# rev_n_v24.net
KiCad netlist of a schematic drawn in EAGLE
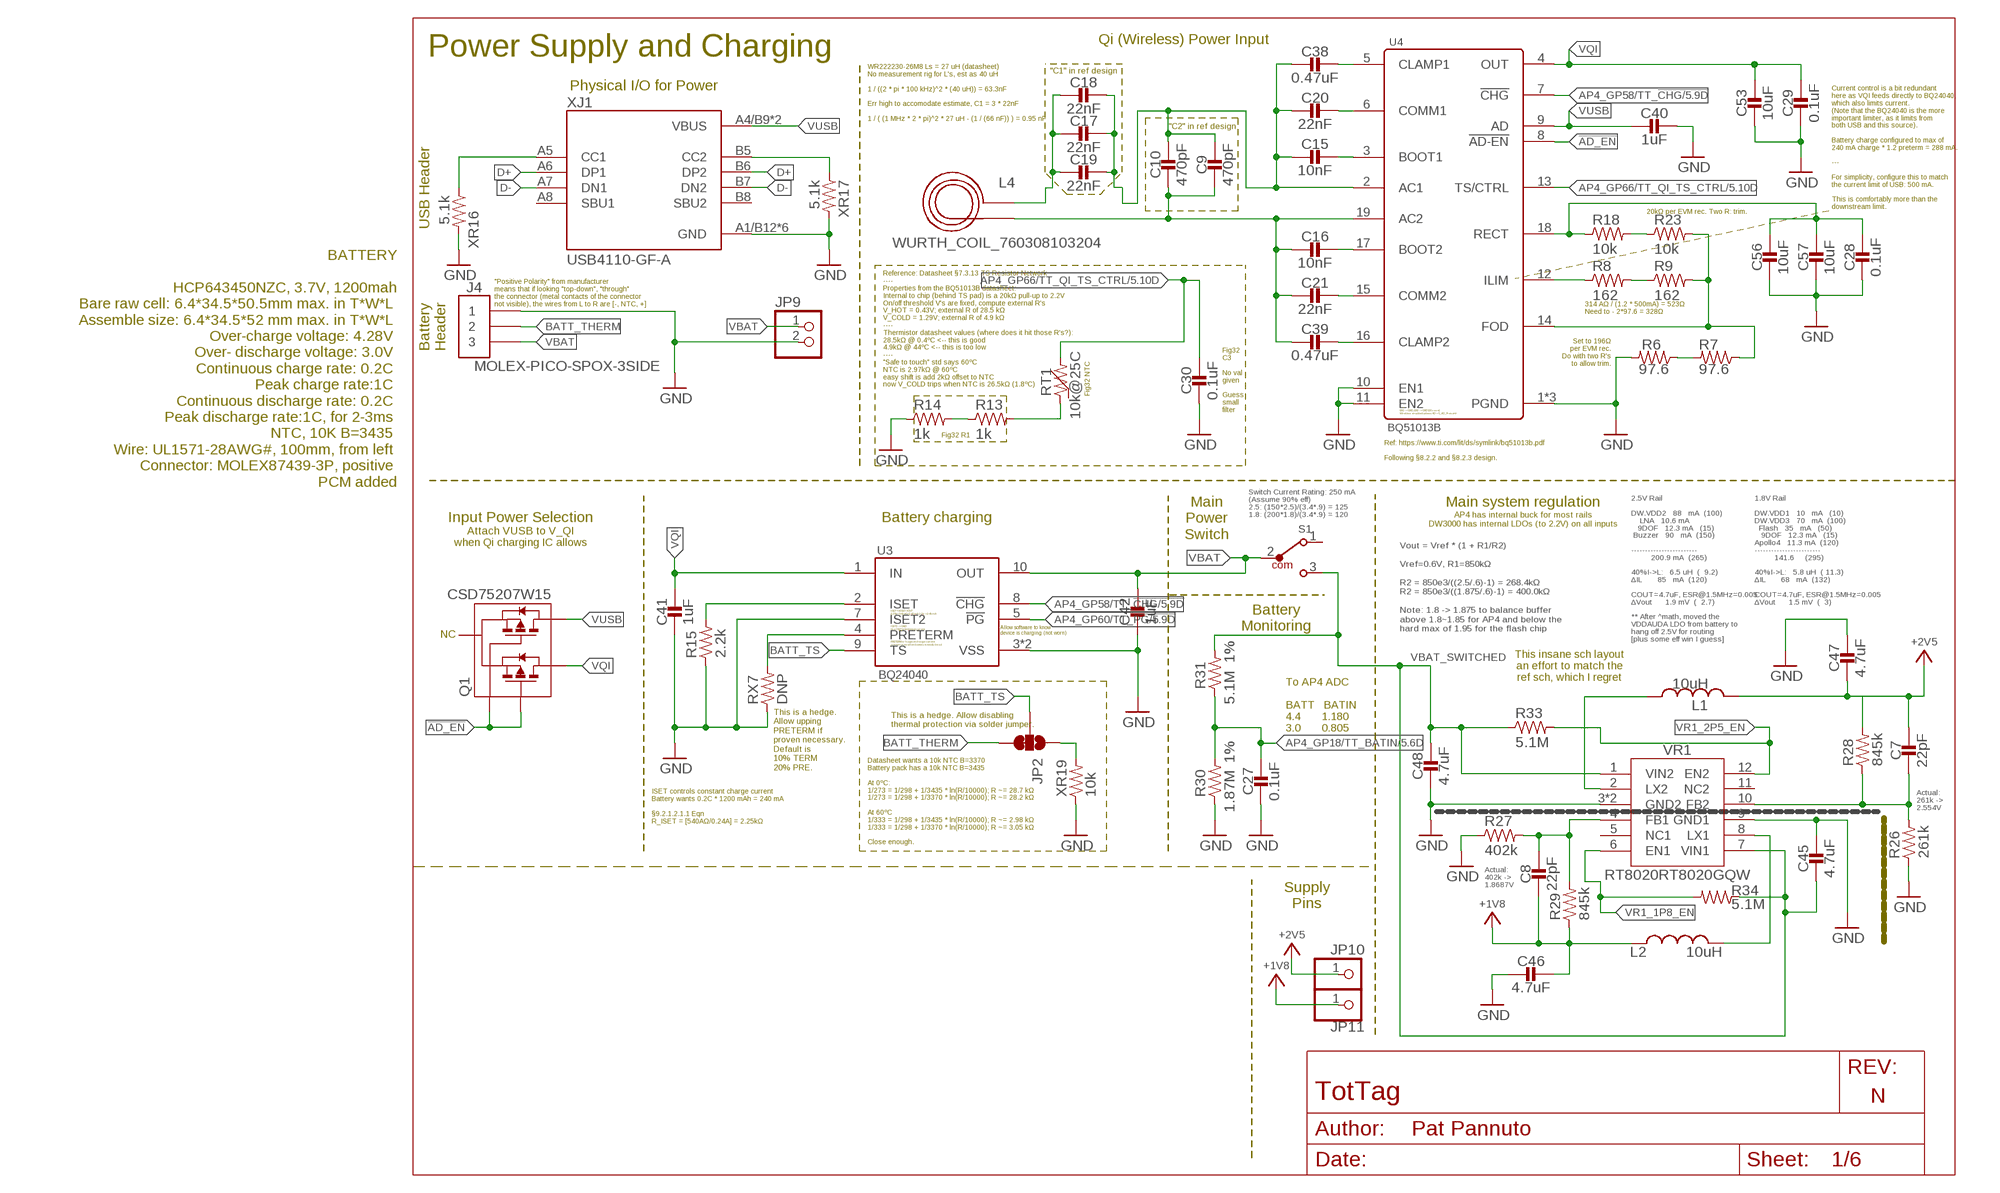
[diagram p0: schematic, sheet 1]
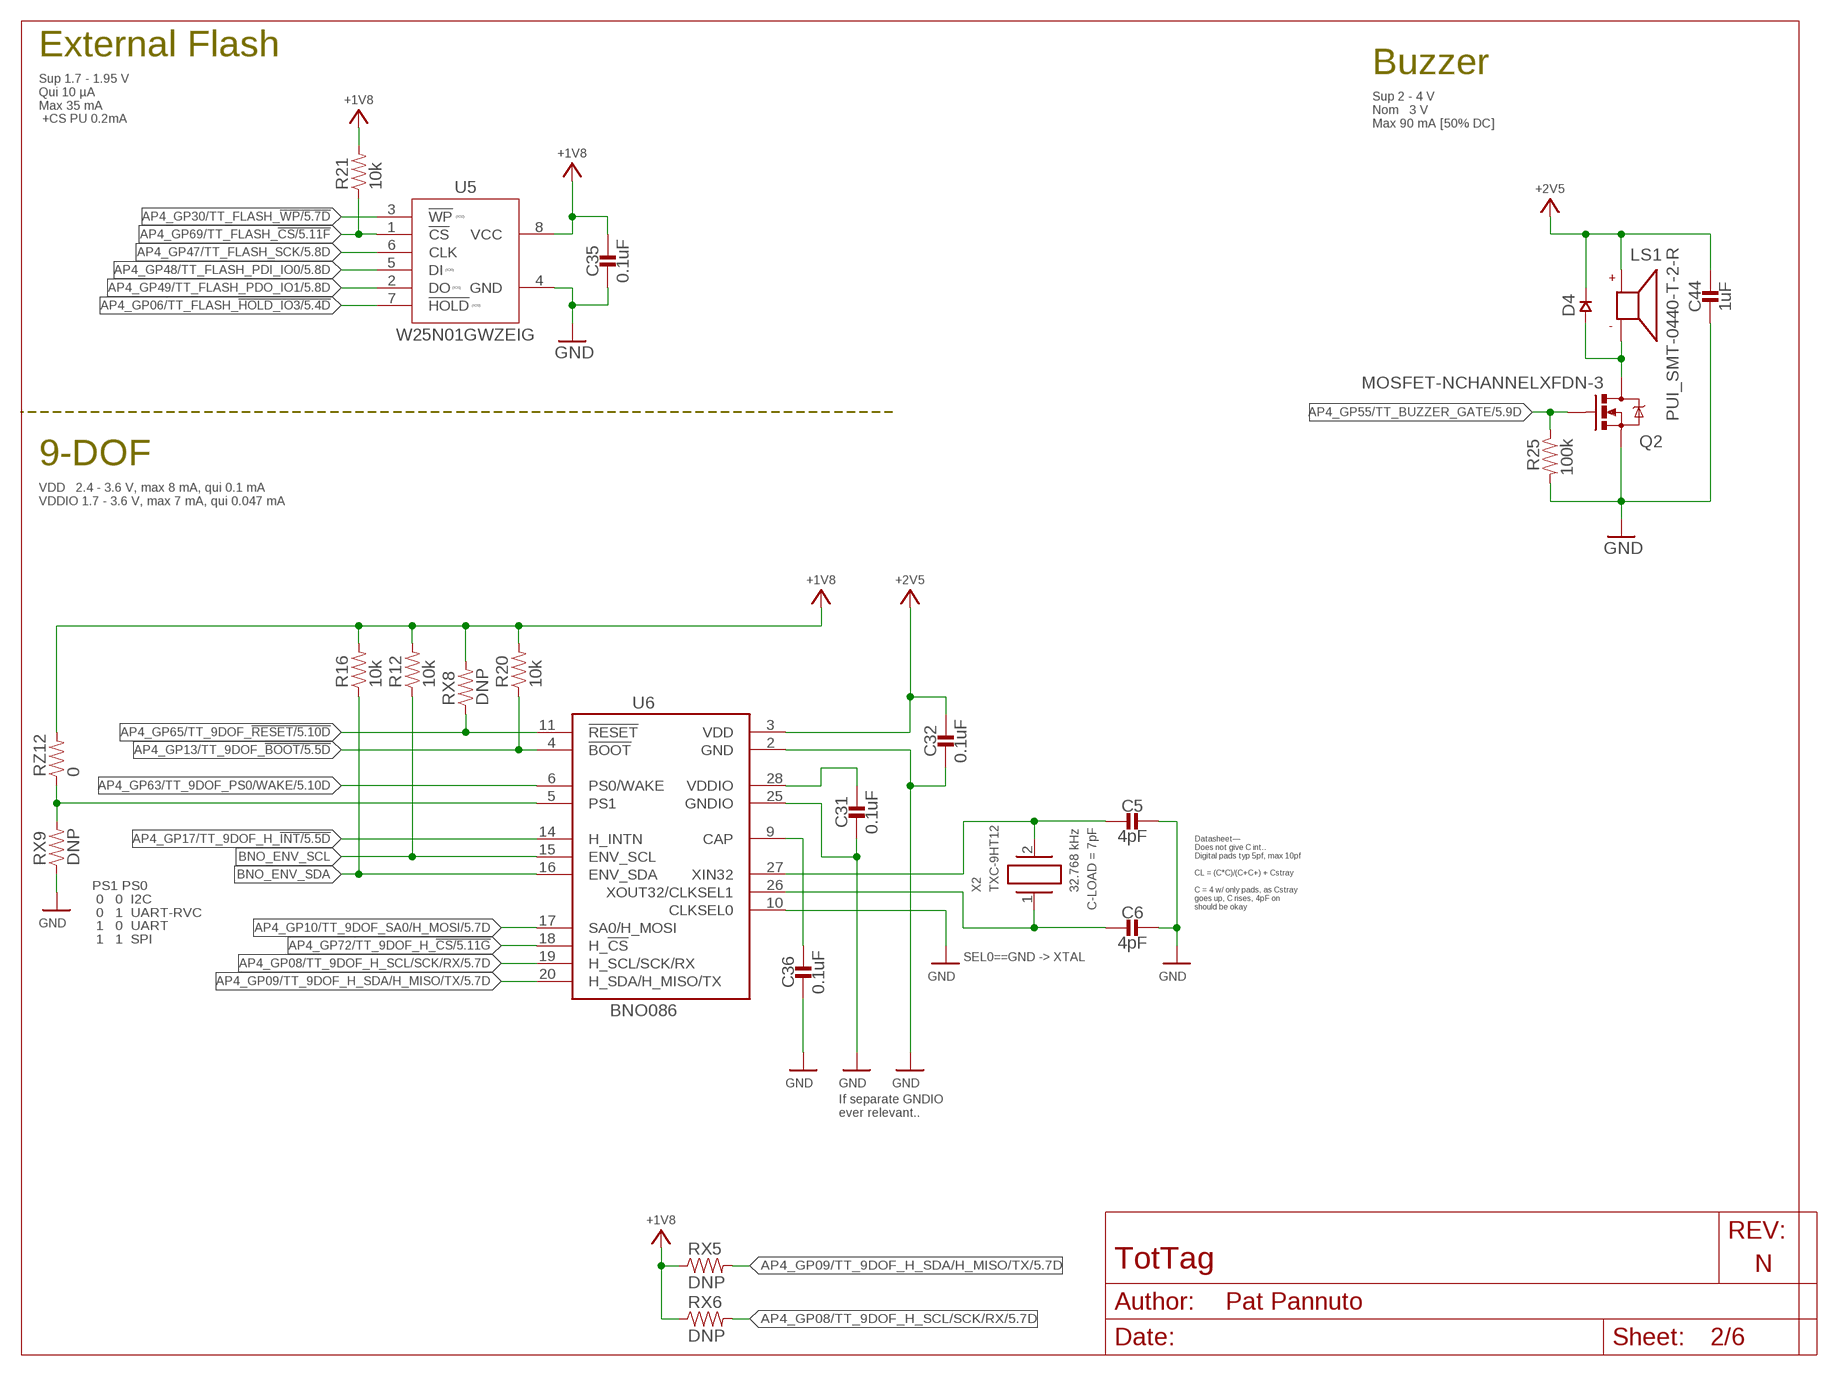
[diagram p1: schematic, sheet 2]
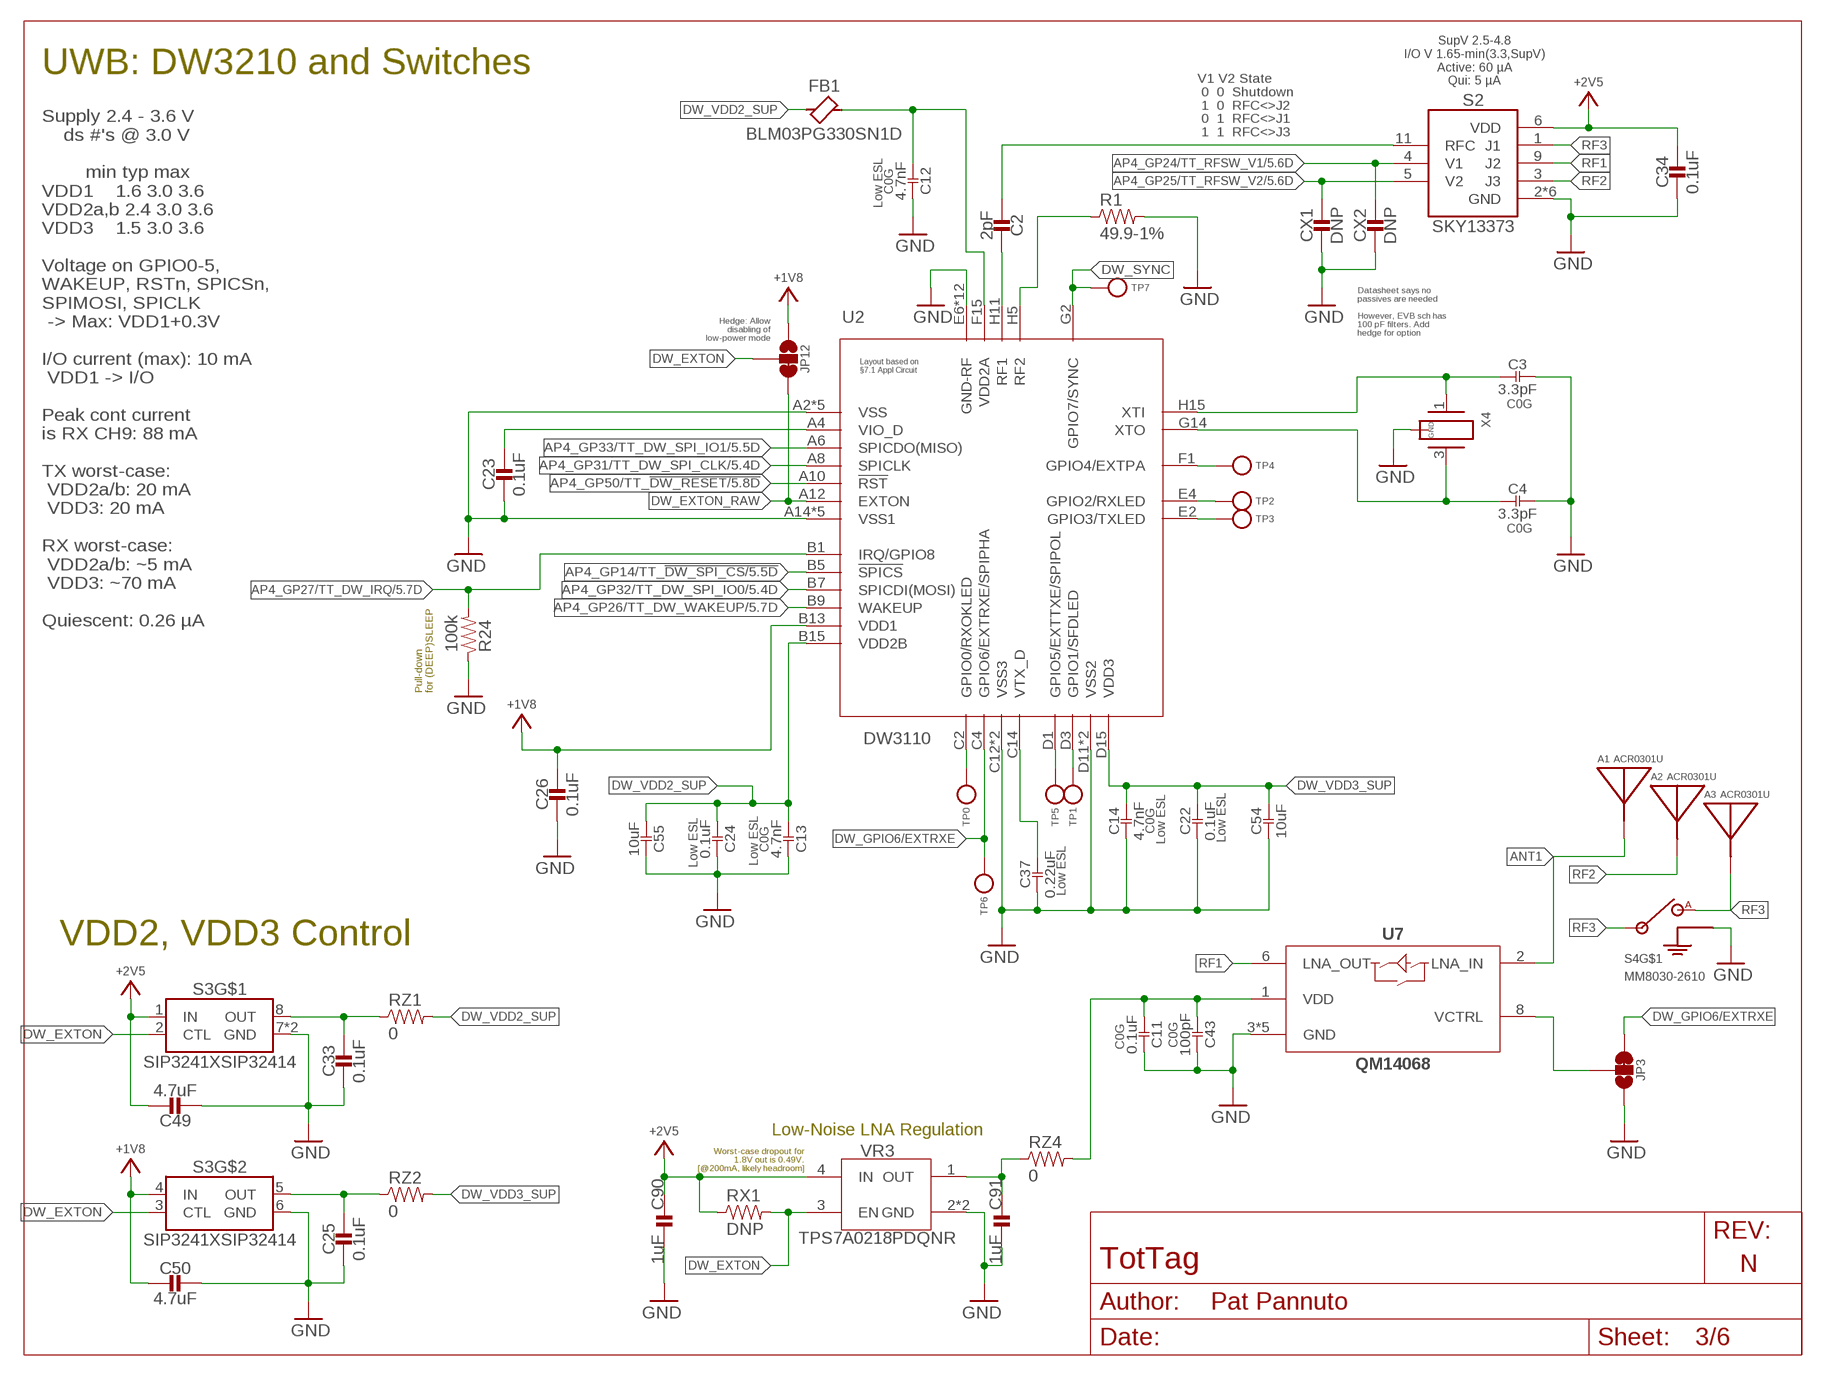
[diagram p2: schematic, sheet 3]
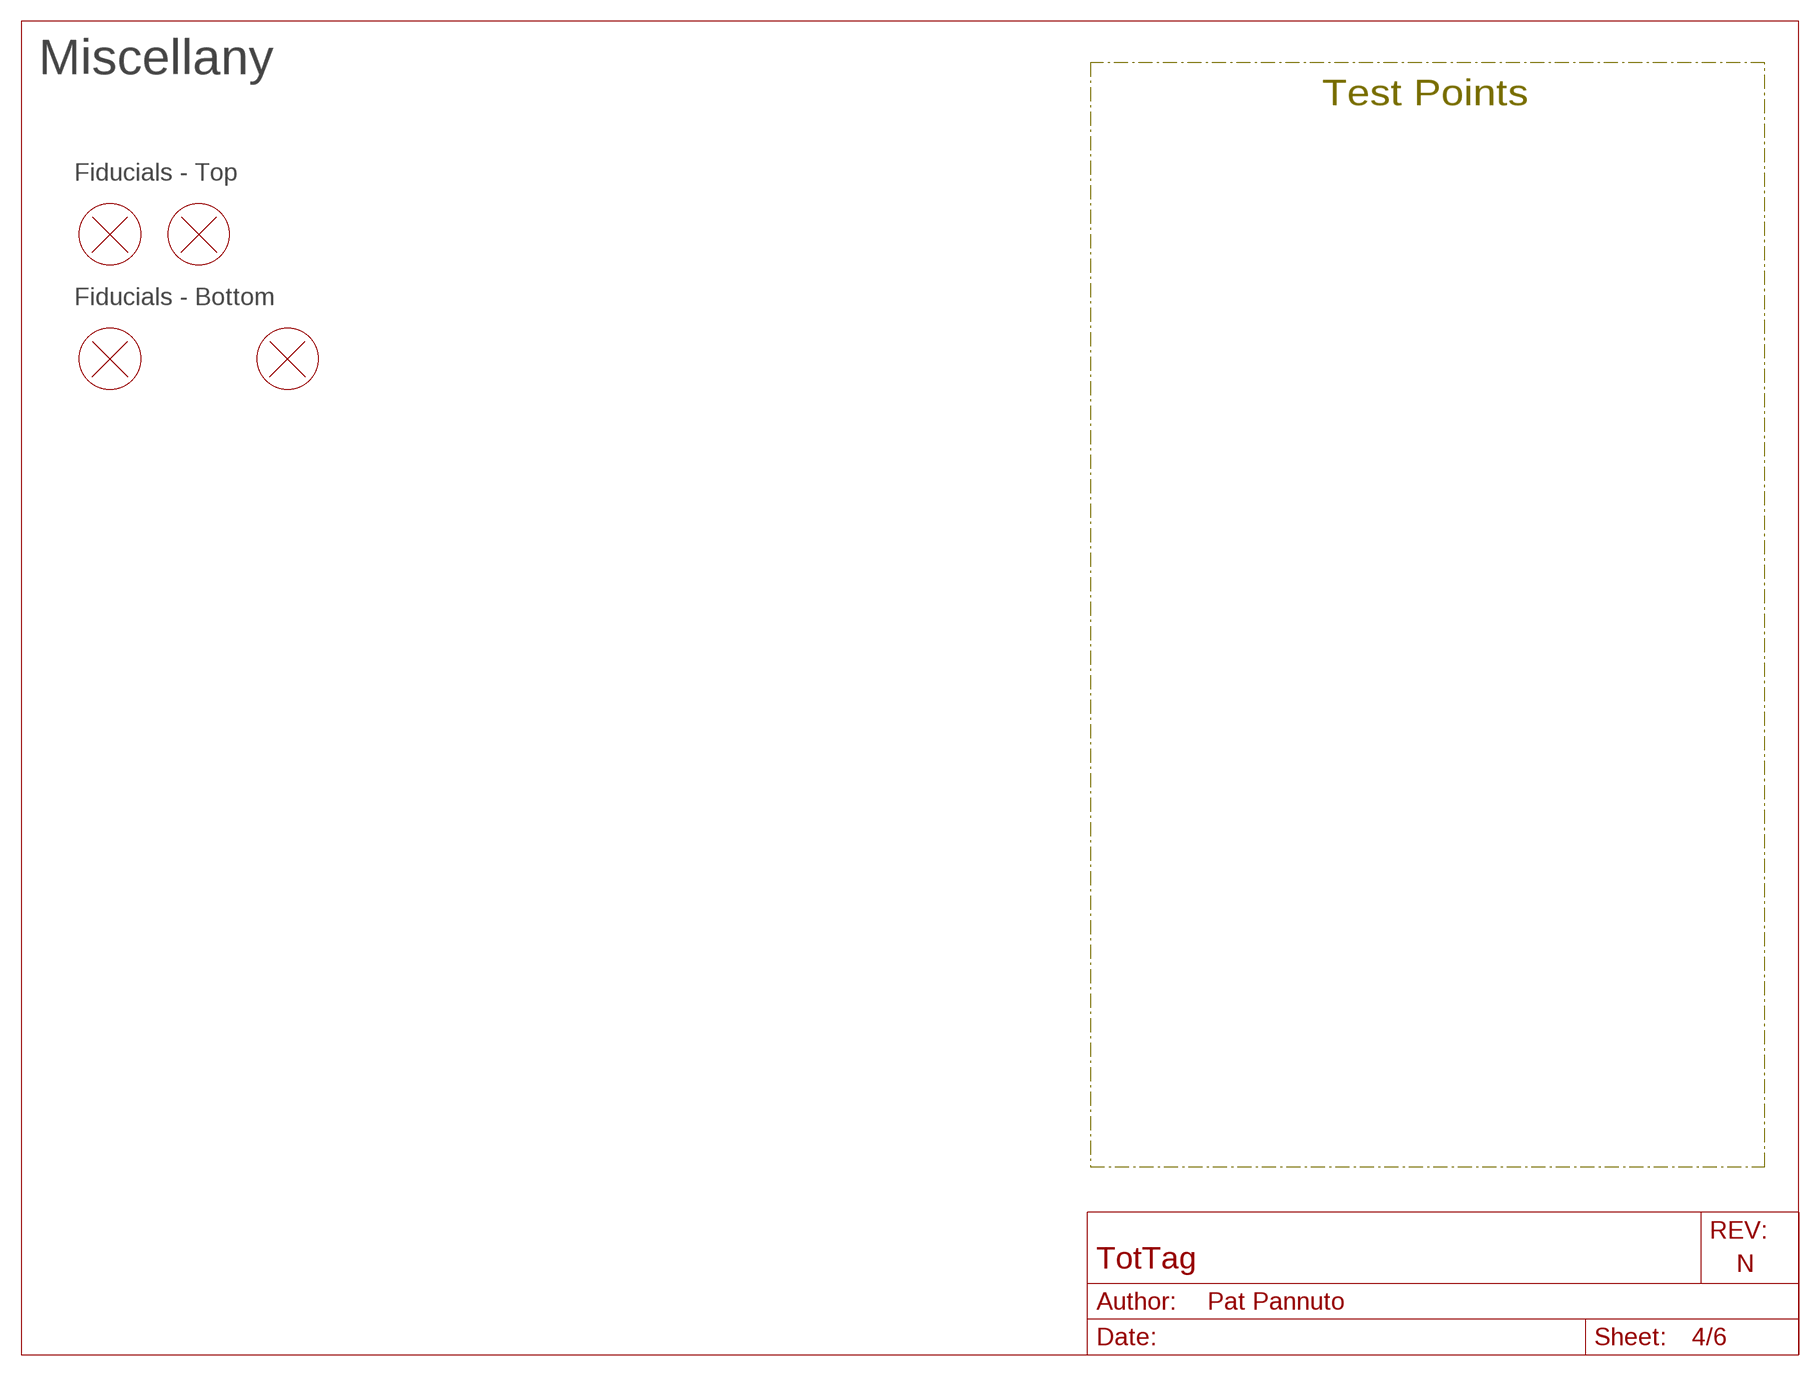
[diagram p3: schematic, sheet 4]
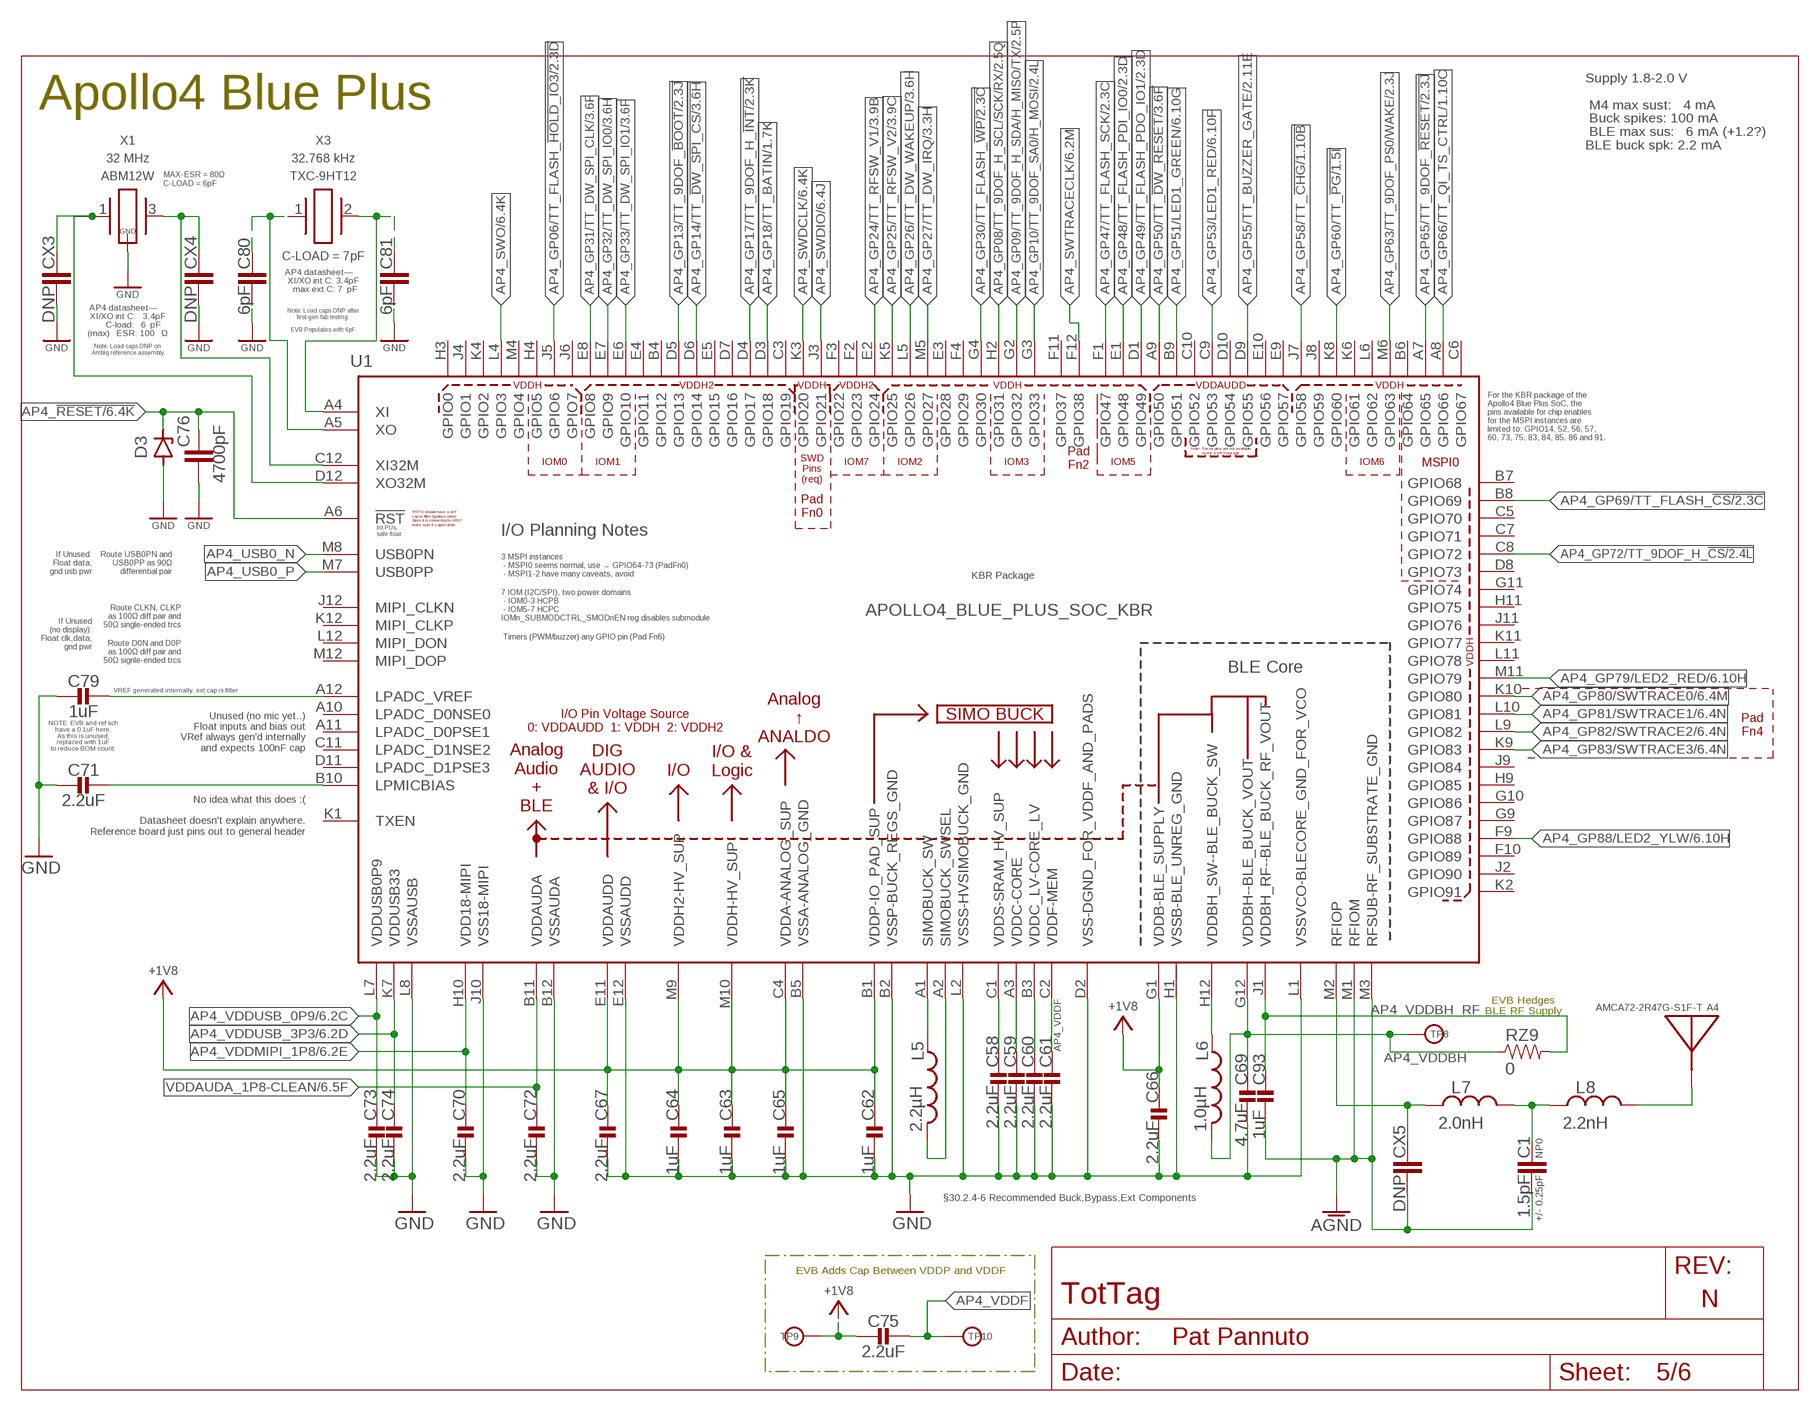
[diagram p4: schematic, sheet 5]
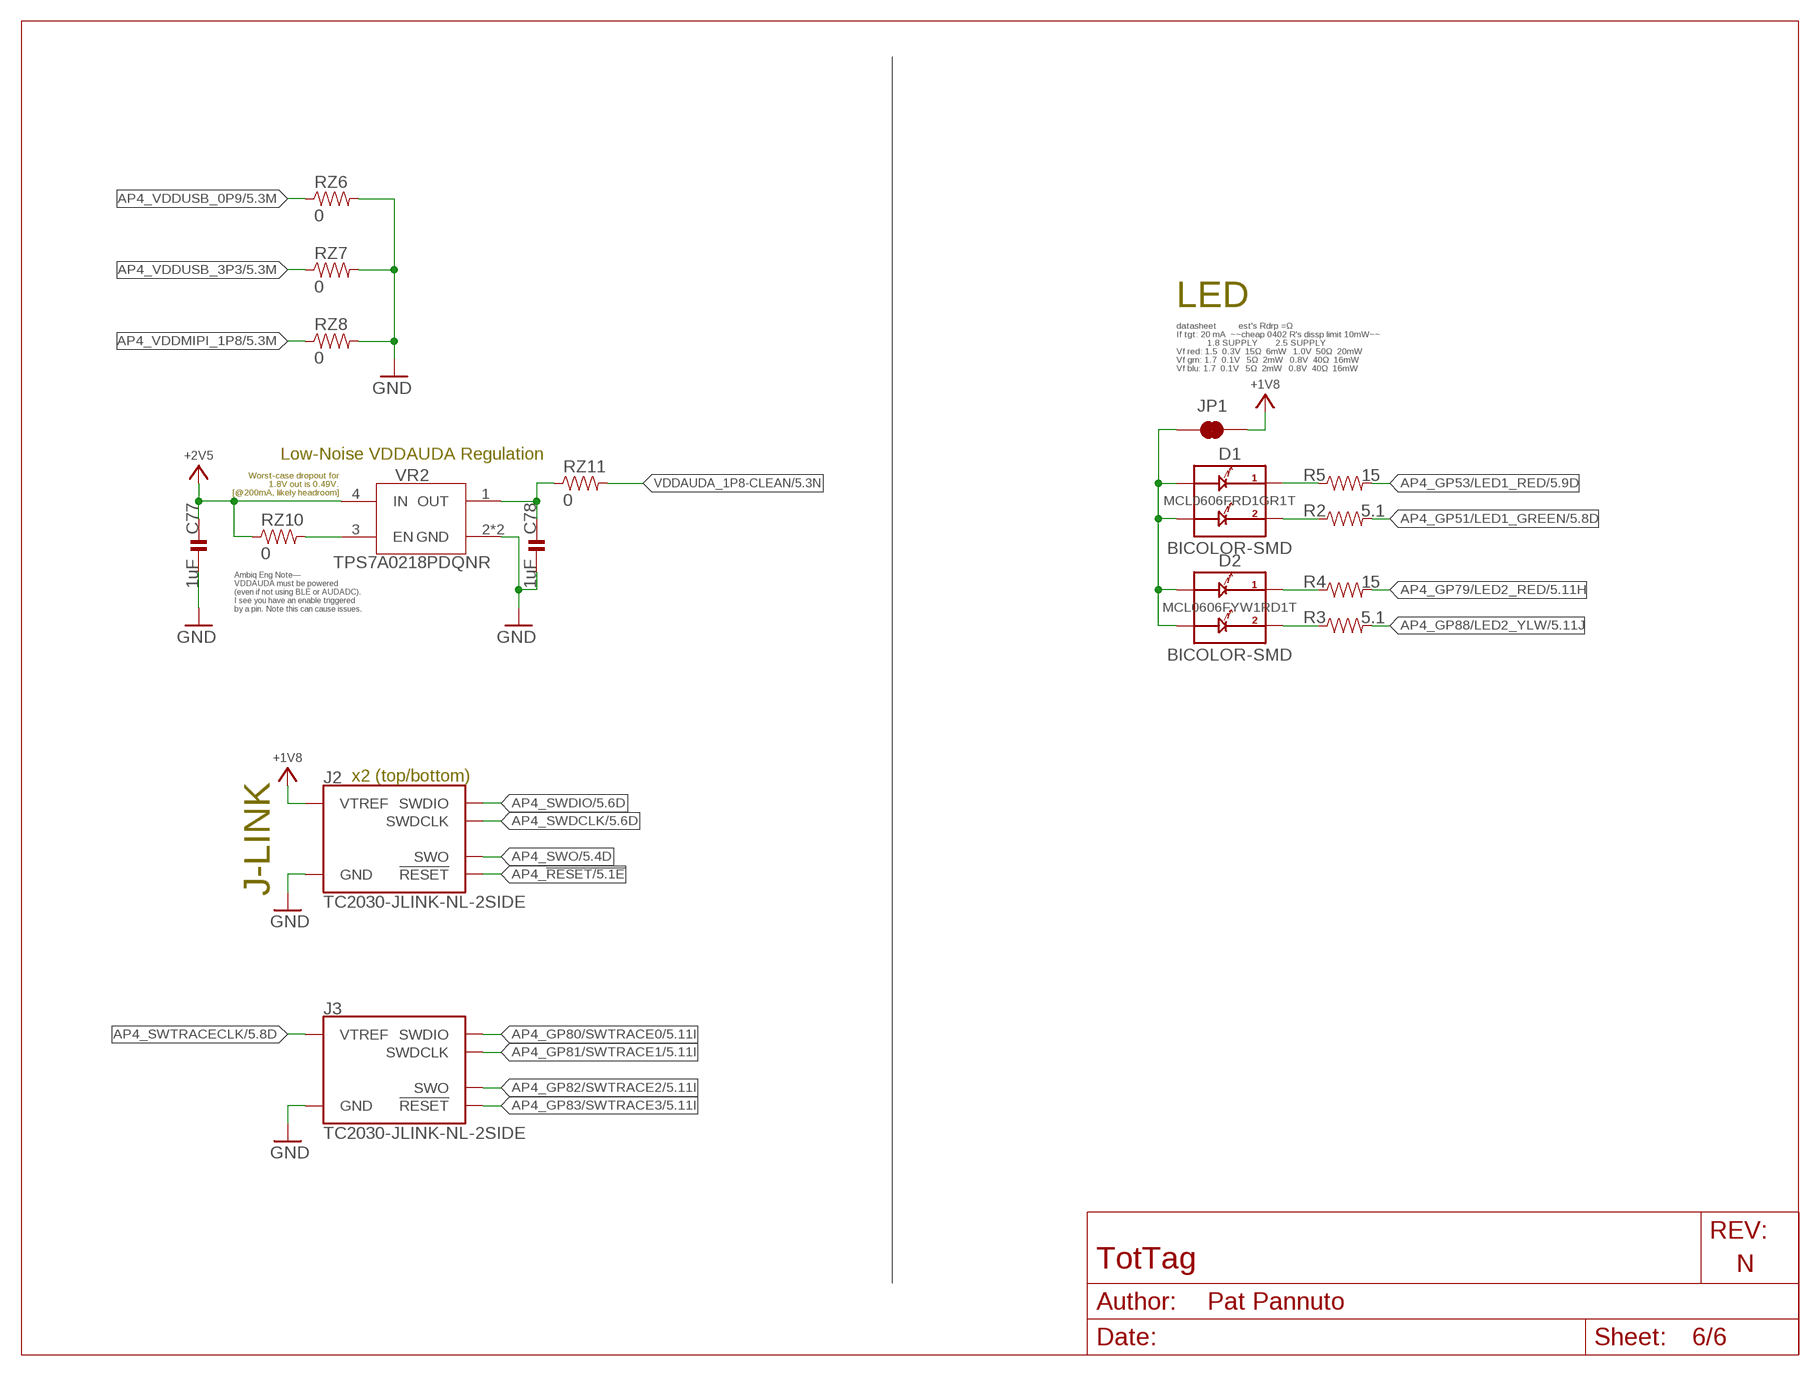
[diagram p5: schematic, sheet 6]

(export (version "E")
  (design (tool "Eeschema 10.0.6"))
  (components
    (comp (ref "FD1")
      (value "FIDUCIAL")
      (footprint "eagle-import:FIDUCIAL_1MM-CU_2MM-MASK")
      (libsource (lib "eagle-import") (part "FIDUCIAL"))
    )
    (comp (ref "FD2")
      (value "FIDUCIAL")
      (footprint "eagle-import:FIDUCIAL_1MM-CU_2MM-MASK")
      (libsource (lib "eagle-import") (part "FIDUCIAL"))
    )
    (comp (ref "FD4")
      (value "FIDUCIAL")
      (footprint "eagle-import:FIDUCIAL_1MM-CU_2MM-MASK")
      (libsource (lib "eagle-import") (part "FIDUCIAL"))
    )
    (comp (ref "FD6")
      (value "FIDUCIAL")
      (footprint "eagle-import:FIDUCIAL_1MM-CU_2MM-MASK")
      (libsource (lib "eagle-import") (part "FIDUCIAL"))
    )
    (comp (ref "C7")
      (value "22pF")
      (footprint "eagle-import:0201_CAP")
      (fields (field (name "MPN") "GRM0335C1H220FA01D"))
      (libsource (lib "eagle-import") (part "passives_20904581_CAPACITOR0201_CAP"))
    )
    (comp (ref "C8")
      (value "22pF")
      (footprint "eagle-import:0201_CAP")
      (fields (field (name "MPN") "GRM0335C1H220FA01D"))
      (libsource (lib "eagle-import") (part "passives_20904581_CAPACITOR0201_CAP"))
    )
    (comp (ref "C9")
      (value "470pF")
      (footprint "eagle-import:0402_CAP")
      (description "CAP CER 470PF 50V C0G/NP0 0402")
      (fields (field (name "MANUFACTURER") "Murata") (field (name "MPN") "GRM1555C1H471JA01J"))
      (libsource (lib "eagle-import") (part "passives_20904581_CAPACITOR0402_CAP"))
    )
    (comp (ref "C10")
      (value "470pF")
      (footprint "eagle-import:0402_CAP")
      (description "CAP CER 470PF 50V C0G/NP0 0402")
      (fields (field (name "MANUFACTURER") "Murata") (field (name "MPN") "GRM1555C1H471JA01J"))
      (libsource (lib "eagle-import") (part "passives_20904581_CAPACITOR0402_CAP"))
    )
    (comp (ref "C15")
      (value "10nF")
      (footprint "eagle-import:0402_CAP")
      (fields (field (name "MPN") "GRM155R71H103KA88J"))
      (libsource (lib "eagle-import") (part "passives_20904581_CAPACITOR0402_CAP"))
    )
    (comp (ref "C16")
      (value "10nF")
      (footprint "eagle-import:0402_CAP")
      (fields (field (name "MPN") "GRM155R71H103KA88J"))
      (libsource (lib "eagle-import") (part "passives_20904581_CAPACITOR0402_CAP"))
    )
    (comp (ref "C17")
      (value "22nF")
      (footprint "eagle-import:0402_CAP")
      (fields (field (name "MPN") "GRM155R71E223JA61D"))
      (libsource (lib "eagle-import") (part "passives_20904581_CAPACITOR0402_CAP"))
    )
    (comp (ref "C18")
      (value "22nF")
      (footprint "eagle-import:0402_CAP")
      (fields (field (name "MPN") "GRM155R71E223JA61D"))
      (libsource (lib "eagle-import") (part "passives_20904581_CAPACITOR0402_CAP"))
    )
    (comp (ref "C19")
      (value "22nF")
      (footprint "eagle-import:0402_CAP")
      (fields (field (name "MPN") "GRM155R71E223JA61D"))
      (libsource (lib "eagle-import") (part "passives_20904581_CAPACITOR0402_CAP"))
    )
    (comp (ref "C20")
      (value "22nF")
      (footprint "eagle-import:0402_CAP")
      (fields (field (name "MPN") "CC0402ZRY5V8BB223"))
      (libsource (lib "eagle-import") (part "passives_20904581_CAPACITOR0402_CAP"))
    )
    (comp (ref "C21")
      (value "22nF")
      (footprint "eagle-import:0402_CAP")
      (fields (field (name "MPN") "CC0402ZRY5V8BB223"))
      (libsource (lib "eagle-import") (part "passives_20904581_CAPACITOR0402_CAP"))
    )
    (comp (ref "C27")
      (value "0.1uF")
      (footprint "eagle-import:0402_CAP")
      (fields (field (name "MPN") "GRM155R71C104KA88J "))
      (libsource (lib "eagle-import") (part "CAPACITOR0402_CAP"))
    )
    (comp (ref "C28")
      (value "0.1uF")
      (footprint "eagle-import:0402_CAP")
      (fields (field (name "MPN") "GRM155R71C104KA88J "))
      (libsource (lib "eagle-import") (part "CAPACITOR0402_CAP"))
    )
    (comp (ref "C29")
      (value "0.1uF")
      (footprint "eagle-import:0402_CAP")
      (fields (field (name "MPN") "GRM155R71C104KA88J "))
      (libsource (lib "eagle-import") (part "CAPACITOR0402_CAP"))
    )
    (comp (ref "C30")
      (value "0.1uF")
      (footprint "eagle-import:0402_CAP")
      (fields (field (name "MPN") "GRM155R71C104KA88J "))
      (libsource (lib "eagle-import") (part "CAPACITOR0402_CAP"))
    )
    (comp (ref "C38")
      (value "0.47uF")
      (footprint "eagle-import:0402_CAP")
      (fields (field (name "MPN") "GRT155R61E474ME01D"))
      (libsource (lib "eagle-import") (part "passives_20904581_CAPACITOR0402_CAP"))
    )
    (comp (ref "C39")
      (value "0.47uF")
      (footprint "eagle-import:0402_CAP")
      (fields (field (name "MPN") "GRT155R61E474ME01D"))
      (libsource (lib "eagle-import") (part "passives_20904581_CAPACITOR0402_CAP"))
    )
    (comp (ref "C40")
      (value "1uF")
      (footprint "eagle-import:0402_CAP")
      (fields (field (name "MPN") "GRM155R70J105KA12J"))
      (libsource (lib "eagle-import") (part "CAPACITOR0402_CAP"))
    )
    (comp (ref "C41")
      (value "1uF")
      (footprint "eagle-import:0402_CAP")
      (fields (field (name "MPN") "GRM155R70J105KA12J"))
      (libsource (lib "eagle-import") (part "CAPACITOR0402_CAP"))
    )
    (comp (ref "C42")
      (value "1uF")
      (footprint "eagle-import:0402_CAP")
      (fields (field (name "MPN") "GRM155R70J105KA12J"))
      (libsource (lib "eagle-import") (part "CAPACITOR0402_CAP"))
    )
    (comp (ref "C45")
      (value "4.7uF")
      (footprint "eagle-import:0603_CAP")
      (fields (field (name "MPN") "C1608X7S1A475K080AC"))
      (libsource (lib "eagle-import") (part "passives_20904581_CAPACITOR0603_CAP"))
    )
    (comp (ref "C46")
      (value "4.7uF")
      (footprint "eagle-import:0603_CAP")
      (fields (field (name "MPN") "C1608X7S1A475K080AC"))
      (libsource (lib "eagle-import") (part "passives_20904581_CAPACITOR0603_CAP"))
    )
    (comp (ref "C47")
      (value "4.7uF")
      (footprint "eagle-import:0603_CAP")
      (fields (field (name "MPN") "C1608X7S1A475K080AC"))
      (libsource (lib "eagle-import") (part "passives_20904581_CAPACITOR0603_CAP"))
    )
    (comp (ref "C48")
      (value "4.7uF")
      (footprint "eagle-import:0603_CAP")
      (fields (field (name "MPN") "C1608X7S1A475K080AC"))
      (libsource (lib "eagle-import") (part "passives_20904581_CAPACITOR0603_CAP"))
    )
    (comp (ref "C53")
      (value "10uF")
      (footprint "eagle-import:0603_CAP")
      (fields (field (name "MPN") "CM105X5R106M25AT"))
      (libsource (lib "eagle-import") (part "passives_20904581_CAPACITOR0603_CAP"))
    )
    (comp (ref "C56")
      (value "10uF")
      (footprint "eagle-import:0603_CAP")
      (fields (field (name "MPN") "CM105X5R106M25AT"))
      (libsource (lib "eagle-import") (part "passives_20904581_CAPACITOR0603_CAP"))
    )
    (comp (ref "C57")
      (value "10uF")
      (footprint "eagle-import:0603_CAP")
      (fields (field (name "MPN") "CM105X5R106M25AT"))
      (libsource (lib "eagle-import") (part "passives_20904581_CAPACITOR0603_CAP"))
    )
    (comp (ref "J4")
      (value "MOLEX-PICO-SPOX-3SIDE")
      (footprint "eagle-import:MOLEX-PICO-SPOX-3_SIDE")
      (libsource (lib "eagle-import") (part "MOLEX-PICO-SPOX-3SIDE"))
    )
    (comp (ref "JP2")
      (value "JUMPER-SMT_3_1-NC_TRACE_SILK")
      (footprint "eagle-import:SMT-JUMPER_3_1-NC_TRACE_SILK")
      (libsource (lib "eagle-import") (part "JUMPER-SMT_3_1-NC_TRACE_SILK"))
    )
    (comp (ref "JP9")
      (value "PINHD-1X2")
      (footprint "eagle-import:1X02")
      (libsource (lib "eagle-import") (part "PINHD-1X2"))
    )
    (comp (ref "JP10")
      (value "PINHD-1X1")
      (footprint "eagle-import:1X01")
      (libsource (lib "eagle-import") (part "PINHD-1X1"))
    )
    (comp (ref "JP11")
      (value "PINHD-1X1")
      (footprint "eagle-import:1X01")
      (libsource (lib "eagle-import") (part "PINHD-1X1"))
    )
    (comp (ref "L1")
      (value "10uH")
      (footprint "eagle-import:NRX3015")
      (fields (field (name "MANUFACTURER") "TAIYO YUDEN") (field (name "MPN") "NR3015T100M"))
      (libsource (lib "eagle-import") (part "INDUCTORNRX3015"))
    )
    (comp (ref "L2")
      (value "10uH")
      (footprint "eagle-import:NRX3015")
      (fields (field (name "MANUFACTURER") "TAIYO YUDEN") (field (name "MPN") "NR3015T100M"))
      (libsource (lib "eagle-import") (part "INDUCTORNRX3015"))
    )
    (comp (ref "L4")
      (value "WURTH_COIL_760308103204")
      (footprint "eagle-import:WURTH_COIL_760308103204")
      (fields (field (name "MANUFACTURER") "Würth Elektronik") (field (name "MPN") "760308103204"))
      (libsource (lib "eagle-import") (part "WURTH_COIL_760308103204"))
    )
    (comp (ref "Q1")
      (value "CSD75207W15")
      (footprint "eagle-import:DSBGA")
      (fields (field (name "MANUFACTURER") "TEXAS INSTRUMENTS"))
      (libsource (lib "eagle-import") (part "CSD75207W15"))
    )
    (comp (ref "R6")
      (value "97.6")
      (footprint "eagle-import:0402_RES")
      (fields (field (name "MPN") "RMCF0402FT97R6"))
      (libsource (lib "eagle-import") (part "passives_20904581_RESISTOR0402_RES"))
    )
    (comp (ref "R7")
      (value "97.6")
      (footprint "eagle-import:0402_RES")
      (fields (field (name "MPN") "RMCF0402FT97R6"))
      (libsource (lib "eagle-import") (part "passives_20904581_RESISTOR0402_RES"))
    )
    (comp (ref "R8")
      (value "162")
      (footprint "eagle-import:0402_RES")
      (fields (field (name "MPN") "RMCF0402FT162R"))
      (libsource (lib "eagle-import") (part "passives_20904581_RESISTOR0402_RES"))
    )
    (comp (ref "R9")
      (value "162")
      (footprint "eagle-import:0402_RES")
      (fields (field (name "MPN") "RMCF0402FT162R"))
      (libsource (lib "eagle-import") (part "passives_20904581_RESISTOR0402_RES"))
    )
    (comp (ref "R13")
      (value "1k")
      (footprint "eagle-import:0402_RES")
      (libsource (lib "eagle-import") (part "RESISTOR0402_RES"))
    )
    (comp (ref "R14")
      (value "1k")
      (footprint "eagle-import:0402_RES")
      (libsource (lib "eagle-import") (part "RESISTOR0402_RES"))
    )
    (comp (ref "R15")
      (value "2.2k")
      (footprint "eagle-import:0402_RES")
      (fields (field (name "MPN") "RMCF0402JT2K20"))
      (libsource (lib "eagle-import") (part "passives_20904581_RESISTOR0402_RES"))
    )
    (comp (ref "R18")
      (value "10k")
      (footprint "eagle-import:0402_RES")
      (fields (field (name "MPN") "RC0402JR-0710KL"))
      (libsource (lib "eagle-import") (part "RESISTOR0402_RES"))
    )
    (comp (ref "R23")
      (value "10k")
      (footprint "eagle-import:0402_RES")
      (fields (field (name "MPN") "RC0402JR-0710KL"))
      (libsource (lib "eagle-import") (part "RESISTOR0402_RES"))
    )
    (comp (ref "R26")
      (value "261k")
      (footprint "eagle-import:0201_RES")
      (fields (field (name "MPN") "ERJ-1GNF2613C"))
      (libsource (lib "eagle-import") (part "passives_20904581_RESISTOR0201_RES"))
    )
    (comp (ref "R27")
      (value "402k")
      (footprint "eagle-import:0201_RES")
      (fields (field (name "MPN") "ERJ-1GNF4023C"))
      (libsource (lib "eagle-import") (part "passives_20904581_RESISTOR0201_RES"))
    )
    (comp (ref "R28")
      (value "845k")
      (footprint "eagle-import:0201_RES")
      (fields (field (name "MPN") "ERJ-1GNF8453C"))
      (libsource (lib "eagle-import") (part "passives_20904581_RESISTOR0201_RES"))
    )
    (comp (ref "R29")
      (value "845k")
      (footprint "eagle-import:0201_RES")
      (fields (field (name "MPN") "ERJ-1GNF8453C"))
      (libsource (lib "eagle-import") (part "passives_20904581_RESISTOR0201_RES"))
    )
    (comp (ref "R30")
      (value "1.87M")
      (footprint "eagle-import:0402_RES")
      (fields (field (name "MPN") "RMCF0402FT1M87") (field (name "TOLERANCE") "1%"))
      (libsource (lib "eagle-import") (part "RESISTOR0402_RES"))
    )
    (comp (ref "R31")
      (value "5.1M")
      (footprint "eagle-import:0402_RES")
      (fields (field (name "MPN") "RMCF0402FT5M10") (field (name "TOLERANCE") "1%"))
      (libsource (lib "eagle-import") (part "RESISTOR0402_RES"))
    )
    (comp (ref "R33")
      (value "5.1M")
      (footprint "eagle-import:0402_RES")
      (fields (field (name "MPN") "RMCF0402FT5M10"))
      (libsource (lib "eagle-import") (part "RESISTOR0402_RES"))
    )
    (comp (ref "R34")
      (value "5.1M")
      (footprint "eagle-import:0402_RES")
      (fields (field (name "MPN") "RMCF0402FT5M10"))
      (libsource (lib "eagle-import") (part "RESISTOR0402_RES"))
    )
    (comp (ref "RT1")
      (value "10k@25C")
      (footprint "eagle-import:0402_RES")
      (fields (field (name "MPN") "NCU15XH103F60RC"))
      (libsource (lib "eagle-import") (part "THERMISTOR0402"))
    )
    (comp (ref "RX7")
      (value "DNP")
      (footprint "eagle-import:0402_RES")
      (libsource (lib "eagle-import") (part "passives_20904581_RESISTOR0402_RES"))
    )
    (comp (ref "S1")
      (value "450404015514")
      (footprint "eagle-import:450404015514")
      (libsource (lib "eagle-import") (part "450404015514"))
    )
    (comp (ref "U3")
      (value "BQ24040")
      (footprint "eagle-import:DSQ0010A")
      (fields (field (name "MPN") "BQ24040DSQR"))
      (libsource (lib "eagle-import") (part "BQ24040"))
    )
    (comp (ref "U4")
      (value "BQ51013B")
      (footprint "eagle-import:RHL0020A")
      (fields (field (name "MPN") "BQ51013BRHLR"))
      (libsource (lib "eagle-import") (part "BQ51013B"))
    )
    (comp (ref "VR1")
      (value "RT8020RT8020GQW")
      (footprint "eagle-import:SON45P300X300X80-13T160X250N")
      (fields (field (name "MANUFACTURER") "RichTek") (field (name "MPN") "RT8020GQW"))
      (libsource (lib "eagle-import") (part "RT8020RT8020GQW"))
    )
    (comp (ref "XJ1")
      (value "USB4110-GF-A")
      (footprint "eagle-import:GCT_USB4110-GF-A")
      (fields (field (name "MF") "GCT"))
      (libsource (lib "eagle-import") (part "USB4110-GF-A"))
    )
    (comp (ref "XR16")
      (value "5.1k")
      (footprint "eagle-import:0402_RES")
      (fields (field (name "MPN") "RMCF0402FT5K10"))
      (libsource (lib "eagle-import") (part "passives_20904581_RESISTOR0402_RES"))
    )
    (comp (ref "XR17")
      (value "5.1k")
      (footprint "eagle-import:0402_RES")
      (fields (field (name "MPN") "RMCF0402FT5K10"))
      (libsource (lib "eagle-import") (part "passives_20904581_RESISTOR0402_RES"))
    )
    (comp (ref "XR19")
      (value "10k")
      (footprint "eagle-import:0402_RES")
      (fields (field (name "MPN") "RC0402JR-0710KL"))
      (libsource (lib "eagle-import") (part "RESISTOR0402_RES"))
    )
    (comp (ref "C5")
      (value "4pF")
      (footprint "eagle-import:0201_CAP")
      (fields (field (name "MANUFACTURER") "Murata") (field (name "MPN") "GRM0335C1H4R0BA01D"))
      (libsource (lib "eagle-import") (part "passives_20904581_CAPACITOR0201_CAP"))
    )
    (comp (ref "C6")
      (value "4pF")
      (footprint "eagle-import:0201_CAP")
      (fields (field (name "MANUFACTURER") "Murata") (field (name "MPN") "GRM0335C1H4R0BA01D"))
      (libsource (lib "eagle-import") (part "passives_20904581_CAPACITOR0201_CAP"))
    )
    (comp (ref "C31")
      (value "0.1uF")
      (footprint "eagle-import:0402_CAP")
      (fields (field (name "MPN") "CL05A104KP5NNNC"))
      (libsource (lib "eagle-import") (part "passives_20904581_CAPACITOR0402_CAP"))
    )
    (comp (ref "C32")
      (value "0.1uF")
      (footprint "eagle-import:0402_CAP")
      (fields (field (name "MPN") "CL05A104KP5NNNC"))
      (libsource (lib "eagle-import") (part "passives_20904581_CAPACITOR0402_CAP"))
    )
    (comp (ref "C35")
      (value "0.1uF")
      (footprint "eagle-import:0402_CAP")
      (fields (field (name "MPN") "CL05A104KP5NNNC"))
      (libsource (lib "eagle-import") (part "passives_20904581_CAPACITOR0402_CAP"))
    )
    (comp (ref "C36")
      (value "0.1uF")
      (footprint "eagle-import:0402_CAP")
      (fields (field (name "MPN") "CL05A104KP5NNNC"))
      (libsource (lib "eagle-import") (part "CAPACITOR0402_CAP"))
    )
    (comp (ref "C44")
      (value "1uF")
      (footprint "eagle-import:0402_CAP")
      (fields (field (name "MPN") "GRM155R70J105KA12J"))
      (libsource (lib "eagle-import") (part "CAPACITOR0402_CAP"))
    )
    (comp (ref "D4")
      (value "DIODE0402")
      (footprint "eagle-import:0402_DIODE")
      (fields (field (name "MPN") "CDSQR400B-HF"))
      (libsource (lib "eagle-import") (part "DIODE0402"))
    )
    (comp (ref "LS1")
      (value "PUI_SMT-0440-T-2-R")
      (footprint "eagle-import:SMT-0440-T-2-R")
      (fields (field (name "MPN") "SMT-0440-T-2-R"))
      (libsource (lib "eagle-import") (part "PUI_SMT-0440-T-2-R"))
    )
    (comp (ref "Q2")
      (value "MOSFET-NCHANNELXFDN-3")
      (footprint "eagle-import:XFDFN-3")
      (libsource (lib "eagle-import") (part "MOSFET-NCHANNELXFDN-3"))
    )
    (comp (ref "R12")
      (value "10k")
      (footprint "eagle-import:0402_RES")
      (fields (field (name "MPN") "RC0402JR-0710KL"))
      (libsource (lib "eagle-import") (part "RESISTOR0402_RES"))
    )
    (comp (ref "R16")
      (value "10k")
      (footprint "eagle-import:0402_RES")
      (fields (field (name "MPN") "RC0402JR-0710KL"))
      (libsource (lib "eagle-import") (part "RESISTOR0402_RES"))
    )
    (comp (ref "R20")
      (value "10k")
      (footprint "eagle-import:0402_RES")
      (fields (field (name "MPN") "RC0402JR-0710KL"))
      (libsource (lib "eagle-import") (part "RESISTOR0402_RES"))
    )
    (comp (ref "R21")
      (value "10k")
      (footprint "eagle-import:0402_RES")
      (fields (field (name "MPN") "RC0402JR-0710KL"))
      (libsource (lib "eagle-import") (part "RESISTOR0402_RES"))
    )
    (comp (ref "R25")
      (value "100k")
      (footprint "eagle-import:0402_RES")
      (fields (field (name "MPN") "RT0402BRE07100KL"))
      (libsource (lib "eagle-import") (part "RESISTOR0402_RES"))
    )
    (comp (ref "RX5")
      (value "DNP")
      (footprint "eagle-import:0603-RES")
      (libsource (lib "eagle-import") (part "passives_20904581_RESISTOR0603_RES"))
    )
    (comp (ref "RX6")
      (value "DNP")
      (footprint "eagle-import:0603-RES")
      (libsource (lib "eagle-import") (part "passives_20904581_RESISTOR0603_RES"))
    )
    (comp (ref "RX8")
      (value "DNP")
      (footprint "eagle-import:0603-RES")
      (libsource (lib "eagle-import") (part "passives_20904581_RESISTOR0603_RES"))
    )
    (comp (ref "RX9")
      (value "DNP")
      (footprint "eagle-import:0603-RES")
      (libsource (lib "eagle-import") (part "passives_20904581_RESISTOR0603_RES"))
    )
    (comp (ref "RZ12")
      (value "0")
      (footprint "eagle-import:0402_RES")
      (fields (field (name "MPN") "RMCF0402ZT0R00"))
      (libsource (lib "eagle-import") (part "passives_20904581_RESISTOR0402_RES"))
    )
    (comp (ref "U5")
      (value "W25N01GWZEIG")
      (footprint "eagle-import:WSON127P800X600X80-9T430X340N")
      (fields (field (name "MANUFACTURER") "Winbond"))
      (libsource (lib "eagle-import") (part "W25N01GWZEIG"))
    )
    (comp (ref "U6")
      (value "BNO086")
      (footprint "eagle-import:LGA28R0P510X4_5P2X3P8X1")
      (fields (field (name "MANUFACTURER") "CEVA Technologies, Inc."))
      (libsource (lib "eagle-import") (part "BNO086"))
    )
    (comp (ref "X2")
      (value "TXC-9HT12")
      (footprint "eagle-import:TXC-9HT12")
      (fields
        (field (name "C-LOAD") "7pF")
        (field (name "FREQUENCY") "32.768 kHz")
        (field (name "MANUFACTURER") "TXC Corp")
        (field (name "MPN") "9HT12-32.768KDZY-T")
      )
      (libsource (lib "eagle-import") (part "TXC-9HT12"))
    )
    (comp (ref "A1")
      (value "ACR0301U")
      (footprint "eagle-import:ACR0301U")
      (fields (field (name "MANUFACTURER") "Abracon"))
      (libsource (lib "eagle-import") (part "ACR0301U"))
    )
    (comp (ref "A2")
      (value "ACR0301U")
      (footprint "eagle-import:ACR0301U")
      (fields (field (name "MANUFACTURER") "Abracon"))
      (libsource (lib "eagle-import") (part "ACR0301U"))
    )
    (comp (ref "A3")
      (value "ACR0301U")
      (footprint "eagle-import:ACR0301U")
      (fields (field (name "MANUFACTURER") "Abracon"))
      (libsource (lib "eagle-import") (part "ACR0301U"))
    )
    (comp (ref "C2")
      (value "2pF")
      (footprint "eagle-import:0201_CAP")
      (fields (field (name "MPN") "CBR02C209A5GAC"))
      (libsource (lib "eagle-import") (part "CAPACITOR0201_CAP"))
    )
    (comp (ref "C3")
      (value "3.3pF")
      (footprint "eagle-import:SMD_2012M-0805US-C")
      (fields
        (field (name "EIA") "C0G")
        (field (name "MANUFACTURER") "KYOCERA AVX")
        (field (name "MPN") "600F3R3BT250XT")
      )
      (libsource (lib "eagle-import") (part "C0805US"))
    )
    (comp (ref "C4")
      (value "3.3pF")
      (footprint "eagle-import:SMD_2012M-0805US-C")
      (fields
        (field (name "EIA") "C0G")
        (field (name "MANUFACTURER") "KYOCERA AVX")
        (field (name "MPN") "600F3R3BT250XT")
      )
      (libsource (lib "eagle-import") (part "C0805US"))
    )
    (comp (ref "C11")
      (value "0.1uF")
      (footprint "eagle-import:SMD_3216M-1206US-C")
      (fields (field (name "EIA") "C0G") (field (name "MPN") "GRM31C5C1H104JA01L"))
      (libsource (lib "eagle-import") (part "C1206US"))
    )
    (comp (ref "C12")
      (value "4.7nF")
      (footprint "eagle-import:SMD_1608M-0603US-C")
      (fields
        (field (name "EIA") "C0G")
        (field (name "FEATURES") "Low ESL")
        (field (name "MANUFACTURER") "KEMET")
        (field (name "MPN") "C0603C472J5GAC7867")
      )
      (libsource (lib "eagle-import") (part "C0603US"))
    )
    (comp (ref "C13")
      (value "4.7nF")
      (footprint "eagle-import:SMD_1608M-0603US-C")
      (fields
        (field (name "EIA") "C0G")
        (field (name "FEATURES") "Low ESL")
        (field (name "MANUFACTURER") "KEMET")
        (field (name "MPN") "C0603C472J5GAC7867")
      )
      (libsource (lib "eagle-import") (part "C0603US"))
    )
    (comp (ref "C14")
      (value "4.7nF")
      (footprint "eagle-import:SMD_1608M-0603US-C")
      (fields
        (field (name "EIA") "C0G")
        (field (name "FEATURES") "Low ESL")
        (field (name "MANUFACTURER") "KEMET")
        (field (name "MPN") "C0603C472J5GAC7867")
      )
      (libsource (lib "eagle-import") (part "C0603US"))
    )
    (comp (ref "C22")
      (value "0.1uF")
      (footprint "eagle-import:SMD_1608M-0603US-C")
      (fields (field (name "FEATURES") "Low ESL") (field (name "MPN") "C1608X7R1H104K080AA"))
      (libsource (lib "eagle-import") (part "C0603US"))
    )
    (comp (ref "C23")
      (value "0.1uF")
      (footprint "eagle-import:0402_CAP")
      (fields (field (name "MPN") "CL05A104KP5NNNC"))
      (libsource (lib "eagle-import") (part "passives_20904581_CAPACITOR0402_CAP"))
    )
    (comp (ref "C24")
      (value "0.1uF")
      (footprint "eagle-import:SMD_1608M-0603US-C")
      (fields (field (name "FEATURES") "Low ESL") (field (name "MPN") "C1608X7R1H104K080AA"))
      (libsource (lib "eagle-import") (part "C0603US"))
    )
    (comp (ref "C25")
      (value "0.1uF")
      (footprint "eagle-import:0402_CAP")
      (fields (field (name "MPN") "CL05A104KP5NNNC"))
      (libsource (lib "eagle-import") (part "passives_20904581_CAPACITOR0402_CAP"))
    )
    (comp (ref "C26")
      (value "0.1uF")
      (footprint "eagle-import:0402_CAP")
      (fields (field (name "MPN") "CL05A104KP5NNNC"))
      (libsource (lib "eagle-import") (part "passives_20904581_CAPACITOR0402_CAP"))
    )
    (comp (ref "C33")
      (value "0.1uF")
      (footprint "eagle-import:0402_CAP")
      (fields (field (name "MPN") "CL05A104KP5NNNC"))
      (libsource (lib "eagle-import") (part "passives_20904581_CAPACITOR0402_CAP"))
    )
    (comp (ref "C34")
      (value "0.1uF")
      (footprint "eagle-import:0402_CAP")
      (fields (field (name "MPN") "CL05A104KP5NNNC"))
      (libsource (lib "eagle-import") (part "passives_20904581_CAPACITOR0402_CAP"))
    )
    (comp (ref "C37")
      (value "0.22uF")
      (footprint "eagle-import:SMD_1608M-0603US-C")
      (fields (field (name "FEATURES") "Low ESL") (field (name "MPN") "C1608X7R1H224K080AB"))
      (libsource (lib "eagle-import") (part "C0603US"))
    )
    (comp (ref "C43")
      (value "100pF")
      (footprint "eagle-import:SMD_1005M-0402US-C")
      (fields (field (name "EIA") "C0G") (field (name "MPN") "C0402C101J3GACTU"))
      (libsource (lib "eagle-import") (part "C0402US"))
    )
    (comp (ref "C49")
      (value "4.7uF")
      (footprint "eagle-import:0603_CAP")
      (fields (field (name "MPN") "C1608X7S1A475K080AC"))
      (libsource (lib "eagle-import") (part "passives_20904581_CAPACITOR0603_CAP"))
    )
    (comp (ref "C50")
      (value "4.7uF")
      (footprint "eagle-import:0603_CAP")
      (fields (field (name "MPN") "C1608X7S1A475K080AC"))
      (libsource (lib "eagle-import") (part "passives_20904581_CAPACITOR0603_CAP"))
    )
    (comp (ref "C54")
      (value "10uF")
      (footprint "eagle-import:SMD_1608M-0603US-C")
      (fields (field (name "MPN") "CM105X5R106M25AT"))
      (libsource (lib "eagle-import") (part "C0603US"))
    )
    (comp (ref "C55")
      (value "10uF")
      (footprint "eagle-import:SMD_1608M-0603US-C")
      (fields (field (name "MPN") "CM105X5R106M25AT"))
      (libsource (lib "eagle-import") (part "C0603US"))
    )
    (comp (ref "C90")
      (value "1uF")
      (footprint "eagle-import:0201_CAP")
      (fields (field (name "MANUFACTURER") "Murata") (field (name "MPN") "GRM033R61A105ME44D"))
      (libsource (lib "eagle-import") (part "passives_20904581_CAPACITOR0201_CAP"))
    )
    (comp (ref "C91")
      (value "1uF")
      (footprint "eagle-import:0201_CAP")
      (fields (field (name "MANUFACTURER") "Murata") (field (name "MPN") "GRM033R61A105ME44D"))
      (libsource (lib "eagle-import") (part "passives_20904581_CAPACITOR0201_CAP"))
    )
    (comp (ref "CX1")
      (value "DNP")
      (footprint "eagle-import:0603_CAP")
      (libsource (lib "eagle-import") (part "passives_20904581_CAPACITOR0603_CAP"))
    )
    (comp (ref "CX2")
      (value "DNP")
      (footprint "eagle-import:0603_CAP")
      (libsource (lib "eagle-import") (part "passives_20904581_CAPACITOR0603_CAP"))
    )
    (comp (ref "FB1")
      (value "BLM03PG330SN1D")
      (footprint "eagle-import:0201_FB")
      (fields (field (name "MANUFACTURER") "Murata"))
      (libsource (lib "eagle-import") (part "FERRITE_BEAD0201"))
    )
    (comp (ref "JP3")
      (value "JUMPER-SMT_3_1-NC_TRACE_SILK")
      (footprint "eagle-import:SMT-JUMPER_3_1-NC_TRACE_SILK")
      (libsource (lib "eagle-import") (part "JUMPER-SMT_3_1-NC_TRACE_SILK"))
    )
    (comp (ref "JP12")
      (value "JUMPER-SMT_3_1-NC_TRACE_SILK")
      (footprint "eagle-import:SMT-JUMPER_3_1-NC_TRACE_SILK")
      (libsource (lib "eagle-import") (part "JUMPER-SMT_3_1-NC_TRACE_SILK"))
    )
    (comp (ref "R1")
      (value "49.9-1%")
      (footprint "eagle-import:0201_RES")
      (fields (field (name "MPN") "ERJ-1GNF49R9C"))
      (libsource (lib "eagle-import") (part "passives_20904581_RESISTOR0201_RES"))
    )
    (comp (ref "R24")
      (value "100k")
      (footprint "eagle-import:0402_RES")
      (fields (field (name "MPN") "RT0402BRE07100KL"))
      (libsource (lib "eagle-import") (part "RESISTOR0402_RES"))
    )
    (comp (ref "RX1")
      (value "DNP")
      (footprint "eagle-import:0603-RES")
      (libsource (lib "eagle-import") (part "passives_20904581_RESISTOR0603_RES"))
    )
    (comp (ref "RZ1")
      (value "0")
      (footprint "eagle-import:0603-RES")
      (fields (field (name "MPN") "RMCF0603ZT0R00"))
      (libsource (lib "eagle-import") (part "passives_20904581_RESISTOR0603_RES"))
    )
    (comp (ref "RZ2")
      (value "0")
      (footprint "eagle-import:0603-RES")
      (fields (field (name "MPN") "RMCF0603ZT0R00"))
      (libsource (lib "eagle-import") (part "passives_20904581_RESISTOR0603_RES"))
    )
    (comp (ref "RZ4")
      (value "0")
      (footprint "eagle-import:0402_RES")
      (fields (field (name "MPN") "RMCF0402ZT0R00"))
      (libsource (lib "eagle-import") (part "passives_20904581_RESISTOR0402_RES"))
    )
    (comp (ref "S2")
      (value "SKY13373")
      (footprint "eagle-import:SKY13373")
      (fields (field (name "MANUFACTURER") "Skyworks") (field (name "MPN") "SKY13373-460LF"))
      (libsource (lib "eagle-import") (part "SKY13373"))
    )
    (comp (ref "S3")
      (value "SIP3241XSIP32414")
      (footprint "eagle-import:TDFN2X2X0P6-8")
      (fields (field (name "MANUFACTURER") "Vishay") (field (name "MPN") "SIP32414DNP-T1-GE4"))
      (libsource (lib "eagle-import") (part "SIP3241XSIP32414"))
    )
    (comp (ref "S4")
      (value "MM8030-2610")
      (footprint "eagle-import:MM8030-2610")
      (fields (field (name "MANUFACTURER") "Murata"))
      (libsource (lib "eagle-import") (part "MM8030-2610"))
    )
    (comp (ref "TP0")
      (value "TEST-POINT")
      (footprint "eagle-import:PAD.03X.03")
      (libsource (lib "eagle-import") (part "TEST-POINT"))
    )
    (comp (ref "TP1")
      (value "TEST-POINT")
      (footprint "eagle-import:PAD.03X.03")
      (libsource (lib "eagle-import") (part "TEST-POINT"))
    )
    (comp (ref "TP2")
      (value "TEST-POINT")
      (footprint "eagle-import:PAD.03X.03")
      (libsource (lib "eagle-import") (part "TEST-POINT"))
    )
    (comp (ref "TP3")
      (value "TEST-POINT")
      (footprint "eagle-import:PAD.03X.03")
      (libsource (lib "eagle-import") (part "TEST-POINT"))
    )
    (comp (ref "TP4")
      (value "TEST-POINT")
      (footprint "eagle-import:PAD.03X.03")
      (libsource (lib "eagle-import") (part "TEST-POINT"))
    )
    (comp (ref "TP5")
      (value "TEST-POINT")
      (footprint "eagle-import:PAD.03X.03")
      (libsource (lib "eagle-import") (part "TEST-POINT"))
    )
    (comp (ref "TP6")
      (value "TEST-POINT")
      (footprint "eagle-import:PAD.03X.03")
      (libsource (lib "eagle-import") (part "TEST-POINT"))
    )
    (comp (ref "TP7")
      (value "TEST-POINT")
      (footprint "eagle-import:PAD.03X.03")
      (libsource (lib "eagle-import") (part "TEST-POINT"))
    )
    (comp (ref "U2")
      (value "DW3110")
      (footprint "eagle-import:WLCSP52")
      (fields (field (name "MANUFACTURER") "Qorvo"))
      (libsource (lib "eagle-import") (part "DW3110"))
    )
    (comp (ref "U7")
      (value "QM14068")
      (footprint "eagle-import:QM14068")
      (fields (field (name "MANUFACTURER") "Qorvo"))
      (libsource (lib "eagle-import") (part "QM14068"))
    )
    (comp (ref "VR3")
      (value "TPS7A0218PDQNR")
      (footprint "eagle-import:4-XDFN-EP")
      (libsource (lib "eagle-import") (part "TPS7A0218PDQNR"))
    )
    (comp (ref "X4")
      (value "TXC-8Y")
      (footprint "eagle-import:TXC-8Y")
      (libsource (lib "eagle-import") (part "TXC-8Y"))
    )
    (comp (ref "C77")
      (value "1uF")
      (footprint "eagle-import:0201_CAP")
      (fields (field (name "MANUFACTURER") "Murata") (field (name "MPN") "GRM033R61A105ME44D"))
      (libsource (lib "eagle-import") (part "passives_20904581_CAPACITOR0201_CAP"))
    )
    (comp (ref "C78")
      (value "1uF")
      (footprint "eagle-import:0201_CAP")
      (fields (field (name "MANUFACTURER") "Murata") (field (name "MPN") "GRM033R61A105ME44D"))
      (libsource (lib "eagle-import") (part "passives_20904581_CAPACITOR0201_CAP"))
    )
    (comp (ref "D1")
      (value "BICOLOR-SMD")
      (footprint "eagle-import:LED-0606")
      (fields (field (name "MPN") "MCL0606FRD1GR1T"))
      (libsource (lib "eagle-import") (part "BICOLOR-SMD"))
    )
    (comp (ref "D2")
      (value "BICOLOR-SMD")
      (footprint "eagle-import:LED-0606")
      (fields (field (name "MPN") "MCL0606FYW1RD1T"))
      (libsource (lib "eagle-import") (part "BICOLOR-SMD"))
    )
    (comp (ref "J2")
      (value "TC2030-JLINK-NL-2SIDE")
      (footprint "eagle-import:TC2030-IDC-NL-2SIDE")
      (libsource (lib "eagle-import") (part "TC2030-JLINK-NL-2SIDE"))
    )
    (comp (ref "J3")
      (value "TC2030-JLINK-NL-2SIDE")
      (footprint "eagle-import:TC2030-IDC-NL-2SIDE")
      (libsource (lib "eagle-import") (part "TC2030-JLINK-NL-2SIDE"))
    )
    (comp (ref "JP1")
      (value "JUMPER-SMT_2_NC_TRACE_SILK")
      (footprint "eagle-import:SMT-JUMPER_2_NC_TRACE_SILK")
      (libsource (lib "eagle-import") (part "JUMPER-SMT_2_NC_TRACE_SILK"))
    )
    (comp (ref "R2")
      (value "5.1")
      (footprint "eagle-import:0402_RES")
      (fields (field (name "MPN") "RC0402JR-075R1L"))
      (libsource (lib "eagle-import") (part "RESISTOR0402_RES"))
    )
    (comp (ref "R3")
      (value "5.1")
      (footprint "eagle-import:0402_RES")
      (fields (field (name "MPN") "RC0402JR-075R1L"))
      (libsource (lib "eagle-import") (part "RESISTOR0402_RES"))
    )
    (comp (ref "R4")
      (value "15")
      (footprint "eagle-import:0402_RES")
      (fields (field (name "MPN") "RC0402JR-0715RL"))
      (libsource (lib "eagle-import") (part "RESISTOR0402_RES"))
    )
    (comp (ref "R5")
      (value "15")
      (footprint "eagle-import:0402_RES")
      (fields (field (name "MPN") "RC0402JR-0715RL"))
      (libsource (lib "eagle-import") (part "RESISTOR0402_RES"))
    )
    (comp (ref "RZ6")
      (value "0")
      (footprint "eagle-import:0402_RES")
      (fields (field (name "MPN") "RMCF0402ZT0R00"))
      (libsource (lib "eagle-import") (part "passives_20904581_RESISTOR0402_RES"))
    )
    (comp (ref "RZ7")
      (value "0")
      (footprint "eagle-import:0402_RES")
      (fields (field (name "MPN") "RMCF0402ZT0R00"))
      (libsource (lib "eagle-import") (part "passives_20904581_RESISTOR0402_RES"))
    )
    (comp (ref "RZ8")
      (value "0")
      (footprint "eagle-import:0402_RES")
      (fields (field (name "MPN") "RMCF0402ZT0R00"))
      (libsource (lib "eagle-import") (part "passives_20904581_RESISTOR0402_RES"))
    )
    (comp (ref "RZ10")
      (value "0")
      (footprint "eagle-import:0402_RES")
      (fields (field (name "MPN") "RMCF0402ZT0R00"))
      (libsource (lib "eagle-import") (part "passives_20904581_RESISTOR0402_RES"))
    )
    (comp (ref "RZ11")
      (value "0")
      (footprint "eagle-import:0402_RES")
      (fields (field (name "MPN") "RMCF0402ZT0R00"))
      (libsource (lib "eagle-import") (part "passives_20904581_RESISTOR0402_RES"))
    )
    (comp (ref "VR2")
      (value "TPS7A0218PDQNR")
      (footprint "eagle-import:4-XDFN-EP")
      (libsource (lib "eagle-import") (part "TPS7A0218PDQNR"))
    )
    (comp (ref "A4")
      (value "AMCA72-2R47G-S1F-T")
      (footprint "eagle-import:AMCA72-2R470G-S1F-T")
      (fields (field (name "MPN") "AMCA72-2R470G-S1F-T4"))
      (libsource (lib "eagle-import") (part "AMCA72-2R47G-S1F-T"))
    )
    (comp (ref "C1")
      (value "1.5pF")
      (footprint "eagle-import:CAPC1005X60")
      (description "CAP CER 1.5PF 50V C0G/NP0 0402")
      (fields
        (field (name "MANUFACTURER") "KEMET")
        (field (name "MPN") "C0402C159C5GAC7867")
        (field (name "TEMPCOEFF") "NP0")
        (field (name "TOLERANCE") "+/- 0.25pF")
      )
      (libsource (lib "eagle-import") (part "CCHIP-0402(1005-METRIC)_"))
    )
    (comp (ref "C58")
      (value "2.2uF")
      (footprint "eagle-import:0201_CAP")
      (fields (field (name "MANUFACTURER") "Murata") (field (name "MPN") "GRM033R61A225KE47D"))
      (libsource (lib "eagle-import") (part "passives_20904581_CAPACITOR0201_CAP"))
    )
    (comp (ref "C59")
      (value "2.2uF")
      (footprint "eagle-import:0201_CAP")
      (fields (field (name "MANUFACTURER") "Murata") (field (name "MPN") "GRM033R61A225KE47D"))
      (libsource (lib "eagle-import") (part "passives_20904581_CAPACITOR0201_CAP"))
    )
    (comp (ref "C60")
      (value "2.2uF")
      (footprint "eagle-import:0201_CAP")
      (fields (field (name "MANUFACTURER") "Murata") (field (name "MPN") "GRM033R61A225KE47D"))
      (libsource (lib "eagle-import") (part "passives_20904581_CAPACITOR0201_CAP"))
    )
    (comp (ref "C61")
      (value "2.2uF")
      (footprint "eagle-import:0201_CAP")
      (fields (field (name "MANUFACTURER") "Murata") (field (name "MPN") "GRM033R61A225KE47D"))
      (libsource (lib "eagle-import") (part "passives_20904581_CAPACITOR0201_CAP"))
    )
    (comp (ref "C62")
      (value "1uF")
      (footprint "eagle-import:0201_CAP")
      (fields (field (name "MANUFACTURER") "Murata") (field (name "MPN") "GRM033R61A105ME44D"))
      (libsource (lib "eagle-import") (part "passives_20904581_CAPACITOR0201_CAP"))
    )
    (comp (ref "C63")
      (value "1uF")
      (footprint "eagle-import:0201_CAP")
      (fields (field (name "MANUFACTURER") "Murata") (field (name "MPN") "GRM033R61A105ME44D"))
      (libsource (lib "eagle-import") (part "passives_20904581_CAPACITOR0201_CAP"))
    )
    (comp (ref "C64")
      (value "1uF")
      (footprint "eagle-import:0201_CAP")
      (fields (field (name "MANUFACTURER") "Murata") (field (name "MPN") "GRM033R61A105ME44D"))
      (libsource (lib "eagle-import") (part "passives_20904581_CAPACITOR0201_CAP"))
    )
    (comp (ref "C65")
      (value "1uF")
      (footprint "eagle-import:0201_CAP")
      (fields (field (name "MANUFACTURER") "Murata") (field (name "MPN") "GRM033R61A105ME44D"))
      (libsource (lib "eagle-import") (part "passives_20904581_CAPACITOR0201_CAP"))
    )
    (comp (ref "C66")
      (value "2.2uF")
      (footprint "eagle-import:0201_CAP")
      (fields (field (name "MANUFACTURER") "Murata") (field (name "MPN") "GRM033R61A225KE47D"))
      (libsource (lib "eagle-import") (part "passives_20904581_CAPACITOR0201_CAP"))
    )
    (comp (ref "C67")
      (value "2.2uF")
      (footprint "eagle-import:0201_CAP")
      (fields (field (name "MANUFACTURER") "Murata") (field (name "MPN") "GRM033R61A225KE47D"))
      (libsource (lib "eagle-import") (part "passives_20904581_CAPACITOR0201_CAP"))
    )
    (comp (ref "C69")
      (value "4.7uF")
      (footprint "eagle-import:0402_CAP")
      (fields (field (name "MPN") "CL05A475MP5NRNC"))
      (libsource (lib "eagle-import") (part "CAPACITOR0402_CAP"))
    )
    (comp (ref "C70")
      (value "2.2uF")
      (footprint "eagle-import:0201_CAP")
      (fields (field (name "MANUFACTURER") "Murata") (field (name "MPN") "GRM033R61A225KE47D"))
      (libsource (lib "eagle-import") (part "passives_20904581_CAPACITOR0201_CAP"))
    )
    (comp (ref "C71")
      (value "2.2uF")
      (footprint "eagle-import:0201_CAP")
      (fields (field (name "MANUFACTURER") "Murata") (field (name "MPN") "GRM033R61A225KE47D"))
      (libsource (lib "eagle-import") (part "passives_20904581_CAPACITOR0201_CAP"))
    )
    (comp (ref "C72")
      (value "2.2uF")
      (footprint "eagle-import:0201_CAP")
      (fields (field (name "MANUFACTURER") "Murata") (field (name "MPN") "GRM033R61A225KE47D"))
      (libsource (lib "eagle-import") (part "passives_20904581_CAPACITOR0201_CAP"))
    )
    (comp (ref "C73")
      (value "2.2uF")
      (footprint "eagle-import:0201_CAP")
      (fields (field (name "MANUFACTURER") "Murata") (field (name "MPN") "GRM033R61A225KE47D"))
      (libsource (lib "eagle-import") (part "passives_20904581_CAPACITOR0201_CAP"))
    )
    (comp (ref "C74")
      (value "2.2uF")
      (footprint "eagle-import:0201_CAP")
      (fields (field (name "MANUFACTURER") "Murata") (field (name "MPN") "GRM033R61A225KE47D"))
      (libsource (lib "eagle-import") (part "passives_20904581_CAPACITOR0201_CAP"))
    )
    (comp (ref "C75")
      (value "2.2uF")
      (footprint "eagle-import:0201_CAP")
      (fields (field (name "MANUFACTURER") "Murata") (field (name "MPN") "GRM033R61A225KE47D"))
      (libsource (lib "eagle-import") (part "passives_20904581_CAPACITOR0201_CAP"))
    )
    (comp (ref "C76")
      (value "4700pF")
      (footprint "eagle-import:CAPC1005X60")
      (fields (field (name "MPN") "KGM05AR71E472KH"))
      (libsource (lib "eagle-import") (part "CCHIP-0402(1005-METRIC)_"))
    )
    (comp (ref "C79")
      (value "1uF")
      (footprint "eagle-import:0201_CAP")
      (fields (field (name "MANUFACTURER") "MURATA") (field (name "MPN") "GRM033R61A105ME44D"))
      (libsource (lib "eagle-import") (part "passives_20904581_CAPACITOR0201_CAP"))
    )
    (comp (ref "C80")
      (value "6pF")
      (footprint "eagle-import:CAPC1005X60")
      (fields (field (name "MANUFACTURER") "Murata") (field (name "MPN") "GCM1555C1H6R0BA16D"))
      (libsource (lib "eagle-import") (part "CCHIP-0402(1005-METRIC)_"))
    )
    (comp (ref "C81")
      (value "6pF")
      (footprint "eagle-import:CAPC1005X60")
      (fields (field (name "MANUFACTURER") "Murata") (field (name "MPN") "GCM1555C1H6R0BA16D"))
      (libsource (lib "eagle-import") (part "CCHIP-0402(1005-METRIC)_"))
    )
    (comp (ref "C93")
      (value "1uF")
      (footprint "eagle-import:0201_CAP")
      (fields (field (name "MANUFACTURER") "Murata") (field (name "MPN") "GRM033R61A105ME44D"))
      (libsource (lib "eagle-import") (part "passives_20904581_CAPACITOR0201_CAP"))
    )
    (comp (ref "CX3")
      (value "DNP")
      (footprint "eagle-import:CAPC1005X60")
      (libsource (lib "eagle-import") (part "CCHIP-0402(1005-METRIC)_"))
    )
    (comp (ref "CX4")
      (value "DNP")
      (footprint "eagle-import:CAPC1005X60")
      (libsource (lib "eagle-import") (part "CCHIP-0402(1005-METRIC)_"))
    )
    (comp (ref "CX5")
      (value "DNP")
      (footprint "eagle-import:CAPC1005X60")
      (libsource (lib "eagle-import") (part "CCHIP-0402(1005-METRIC)_"))
    )
    (comp (ref "D3")
      (value "ZENER")
      (footprint "eagle-import:SODFL1608X70")
      (description "DIODE TVS 5.5V STANDOFF 8V BREAKDOWN SC79")
      (fields (field (name "MANUFACTURER") "NXP SEMICONDUCTOR") (field (name "MPN") "PESD5V0X1UB,135"))
      (libsource (lib "eagle-import") (part "ZENERSODFL(1608-METRIC)_"))
    )
    (comp (ref "L5")
      (value "2.2µH")
      (footprint "eagle-import:0805_CAP")
      (fields (field (name "MANUFACTURER") "Murata") (field (name "MPN") "DFE201210U-2R2M=P2"))
      (libsource (lib "eagle-import") (part "INDUCTOR0805"))
    )
    (comp (ref "L6")
      (value "1.0µH")
      (footprint "eagle-import:0603_CAP")
      (fields (field (name "MANUFACTURER") "Murata") (field (name "MPN") "DFE18SAN1R0ME0L"))
      (libsource (lib "eagle-import") (part "INDUCTOR0603"))
    )
    (comp (ref "L7")
      (value "2.0nH")
      (footprint "eagle-import:INDC1006X60N")
      (description "FIXED IND 2.0NH0.1NH SMD")
      (fields
        (field (name "MANUFACTURER") "Central Technologies")
        (field (name "MPN") "CTTF0402F-2N0B")
        (field (name "TOLERANCE") "+/- 0.1 nH")
      )
      (libsource (lib "eagle-import") (part "LCHIP-0402(1006-METRIC)_"))
    )
    (comp (ref "L8")
      (value "2.2nH")
      (footprint "eagle-import:INDC1006X60N")
      (description "FIXED IND 2.2NH0.1NH SMD")
      (fields
        (field (name "MANUFACTURER") "Central Technologies")
        (field (name "MPN") "CTTF0402F-2N2B")
        (field (name "TOLERANCE") "+/- 0.1 nH")
      )
      (libsource (lib "eagle-import") (part "LCHIP-0402(1006-METRIC)_"))
    )
    (comp (ref "RZ9")
      (value "0")
      (footprint "eagle-import:0402_RES")
      (fields (field (name "MPN") "RMCF0402ZT0R00"))
      (libsource (lib "eagle-import") (part "passives_20904581_RESISTOR0402_RES"))
    )
    (comp (ref "TP8")
      (value "VDDBH")
      (footprint "eagle-import:PAD.03X.03")
      (libsource (lib "eagle-import") (part "TEST-POINT"))
    )
    (comp (ref "TP9")
      (value "VDDP")
      (footprint "eagle-import:PAD.03X.03")
      (libsource (lib "eagle-import") (part "TEST-POINT"))
    )
    (comp (ref "TP10")
      (value "VDDF")
      (footprint "eagle-import:PAD.03X.03")
      (libsource (lib "eagle-import") (part "TEST-POINT"))
    )
    (comp (ref "U1")
      (value "APOLLO4_BLUE_PLUS_SOC_KBR")
      (footprint "eagle-import:APOLLO4_BLUE_SOC_BGA")
      (fields (field (name "MANUFACTURER") "Ambiq") (field (name "MPN") "AMA4B2KP-KBR"))
      (libsource (lib "eagle-import") (part "APOLLO4_BLUE_PLUS_SOC_KBR"))
    )
    (comp (ref "X1")
      (value "ABM12W")
      (footprint "eagle-import:ABM12W")
      (fields
        (field (name "C-LOAD") "6pF")
        (field (name "FREQUENCY") "32 MHz")
        (field (name "MANUFACTURER") "Abracon")
        (field (name "MAX-ESR") "80Ω")
        (field (name "MPN") "ABM12W-32.0000MHZ-6-D1X-T3")
      )
      (libsource (lib "eagle-import") (part "ABM12W"))
    )
    (comp (ref "X3")
      (value "TXC-9HT12")
      (footprint "eagle-import:TXC-9HT12")
      (fields
        (field (name "C-LOAD") "7pF")
        (field (name "FREQUENCY") "32.768 kHz")
        (field (name "MANUFACTURER") "TXC Corp")
        (field (name "MPN") "9HT12-32.768KDZY-T")
      )
      (libsource (lib "eagle-import") (part "TXC-9HT12"))
    )
  )
  (nets
    (net (code "1") (name "+1V8") (class "Default")
      (node (ref "C26") (pin "1") (pinfunction "1_1") (pintype "bidirectional"))
      (node (ref "C35") (pin "1") (pinfunction "1_1") (pintype "bidirectional"))
      (node (ref "C46") (pin "1") (pinfunction "1_1") (pintype "bidirectional"))
      (node (ref "C50") (pin "2") (pinfunction "2_2") (pintype "bidirectional"))
      (node (ref "C62") (pin "P$1") (pinfunction "1_P$1") (pintype "bidirectional"))
      (node (ref "C63") (pin "P$1") (pinfunction "1_P$1") (pintype "bidirectional"))
      (node (ref "C64") (pin "P$1") (pinfunction "1_P$1") (pintype "bidirectional"))
      (node (ref "C65") (pin "P$1") (pinfunction "1_P$1") (pintype "bidirectional"))
      (node (ref "C66") (pin "P$1") (pinfunction "1_P$1") (pintype "bidirectional"))
      (node (ref "C67") (pin "P$1") (pinfunction "1_P$1") (pintype "bidirectional"))
      (node (ref "C75") (pin "P$2") (pinfunction "2_P$2") (pintype "bidirectional"))
      (node (ref "C8") (pin "P$2") (pinfunction "2_P$2") (pintype "bidirectional"))
      (node (ref "J2") (pin "1") (pinfunction "VTREF_1") (pintype "bidirectional"))
      (node (ref "J2") (pin "B1") (pinfunction "VTREF_B1") (pintype "bidirectional"))
      (node (ref "JP1") (pin "2") (pinfunction "2_2") (pintype "passive"))
      (node (ref "JP11") (pin "1") (pinfunction "1_1") (pintype "passive"))
      (node (ref "JP12") (pin "1") (pinfunction "1_1") (pintype "passive"))
      (node (ref "L2") (pin "P$1") (pinfunction "1_P$1") (pintype "bidirectional"))
      (node (ref "R12") (pin "2") (pinfunction "2_2") (pintype "passive"))
      (node (ref "R16") (pin "2") (pinfunction "2_2") (pintype "passive"))
      (node (ref "R20") (pin "2") (pinfunction "2_2") (pintype "passive"))
      (node (ref "R21") (pin "2") (pinfunction "2_2") (pintype "passive"))
      (node (ref "R29") (pin "1") (pinfunction "1_1") (pintype "passive"))
      (node (ref "RX5") (pin "1") (pinfunction "1_1") (pintype "passive"))
      (node (ref "RX6") (pin "1") (pinfunction "1_1") (pintype "passive"))
      (node (ref "RX8") (pin "2") (pinfunction "2_2") (pintype "passive"))
      (node (ref "RZ12") (pin "2") (pinfunction "2_2") (pintype "passive"))
      (node (ref "S3") (pin "4") (pinfunction "IN_4") (pintype "bidirectional"))
      (node (ref "TP9") (pin "P$1") (pinfunction "TESTPOINT_P$1") (pintype "bidirectional"))
      (node (ref "U1") (pin "B1") (pinfunction "VDDP-IO_PAD_SUP_B1") (pintype "bidirectional"))
      (node (ref "U1") (pin "C4") (pinfunction "VDDA-ANALOG_SUP_C4") (pintype "bidirectional"))
      (node (ref "U1") (pin "E11") (pinfunction "VDDAUDD_E11") (pintype "bidirectional"))
      (node (ref "U1") (pin "G1") (pinfunction "VDDB-BLE_SUPPLY_G1") (pintype "bidirectional"))
      (node (ref "U1") (pin "M10") (pinfunction "VDDH-HV_SUP_M10") (pintype "bidirectional"))
      (node (ref "U1") (pin "M9") (pinfunction "VDDH2-HV_SUP_M9") (pintype "bidirectional"))
      (node (ref "U2") (pin "B13") (pinfunction "VDD1_B13") (pintype "bidirectional"))
      (node (ref "U5") (pin "8") (pinfunction "VCC_8") (pintype "bidirectional"))
    )
    (net (code "2") (name "+2V5") (class "Default")
      (node (ref "C32") (pin "1") (pinfunction "1_1") (pintype "bidirectional"))
      (node (ref "C34") (pin "1") (pinfunction "1_1") (pintype "bidirectional"))
      (node (ref "C44") (pin "1") (pinfunction "1_1") (pintype "bidirectional"))
      (node (ref "C47") (pin "2") (pinfunction "2_2") (pintype "bidirectional"))
      (node (ref "C49") (pin "1") (pinfunction "1_1") (pintype "bidirectional"))
      (node (ref "C7") (pin "P$1") (pinfunction "1_P$1") (pintype "bidirectional"))
      (node (ref "C77") (pin "P$1") (pinfunction "1_P$1") (pintype "bidirectional"))
      (node (ref "C90") (pin "P$1") (pinfunction "1_P$1") (pintype "bidirectional"))
      (node (ref "D4") (pin "CATHODE") (pinfunction "CATHODE_CATHODE") (pintype "bidirectional"))
      (node (ref "JP10") (pin "1") (pinfunction "1_1") (pintype "passive"))
      (node (ref "L1") (pin "P$2") (pinfunction "2_P$2") (pintype "bidirectional"))
      (node (ref "LS1") (pin "+") (pinfunction "P_+") (pintype "passive"))
      (node (ref "R28") (pin "2") (pinfunction "2_2") (pintype "passive"))
      (node (ref "RX1") (pin "1") (pinfunction "1_1") (pintype "passive"))
      (node (ref "RZ10") (pin "1") (pinfunction "1_1") (pintype "passive"))
      (node (ref "S2") (pin "6") (pinfunction "VDD_6") (pintype "power_in"))
      (node (ref "S3") (pin "1") (pinfunction "IN_1") (pintype "bidirectional"))
      (node (ref "U6") (pin "3") (pinfunction "VDD_3") (pintype "input"))
      (node (ref "VR2") (pin "4") (pinfunction "IN_4") (pintype "bidirectional"))
      (node (ref "VR3") (pin "4") (pinfunction "IN_4") (pintype "bidirectional"))
    )
    (net (code "3") (name "AGND") (class "Default")
      (node (ref "C1") (pin "2") (pinfunction "2_2") (pintype "passive"))
      (node (ref "C93") (pin "P$2") (pinfunction "2_P$2") (pintype "bidirectional"))
      (node (ref "CX5") (pin "2") (pinfunction "2_2") (pintype "passive"))
      (node (ref "U1") (pin "M1") (pinfunction "RFIOM_M1") (pintype "bidirectional"))
      (node (ref "U1") (pin "M3") (pinfunction "RFSUB-RF_SUBSTRATE_GND_M3") (pintype "bidirectional"))
    )
    (net (code "4") (name "ANT1") (class "Default")
      (node (ref "A1") (pin "FEED") (pinfunction "ANTENNA_FEED") (pintype "bidirectional"))
      (node (ref "U7") (pin "2") (pinfunction "LNA_IN_2") (pintype "bidirectional"))
    )
    (net (code "5") (name "AP4_GP06{slash}TT_FLASH_~{HOLD_IO3}") (class "Default")
      (node (ref "U1") (pin "J5") (pinfunction "GPIO6_J5") (pintype "bidirectional"))
      (node (ref "U5") (pin "7") (pinfunction "~{HOLD}_7") (pintype "bidirectional"))
    )
    (net (code "6") (name "AP4_GP08{slash}TT_9DOF_H_SCL{slash}SCK{slash}RX") (class "Default")
      (node (ref "RX6") (pin "2") (pinfunction "2_2") (pintype "passive"))
      (node (ref "U1") (pin "H2") (pinfunction "GPIO31_H2") (pintype "bidirectional"))
      (node (ref "U6") (pin "19") (pinfunction "H_SCL/SCK/RX_19") (pintype "bidirectional"))
    )
    (net (code "7") (name "AP4_GP09{slash}TT_9DOF_H_SDA{slash}H_MISO{slash}TX") (class "Default")
      (node (ref "RX5") (pin "2") (pinfunction "2_2") (pintype "passive"))
      (node (ref "U1") (pin "G2") (pinfunction "GPIO32_G2") (pintype "bidirectional"))
      (node (ref "U6") (pin "20") (pinfunction "H_SDA/H_MISO/TX_20") (pintype "bidirectional"))
    )
    (net (code "8") (name "AP4_GP10{slash}TT_9DOF_SA0{slash}H_MOSI") (class "Default")
      (node (ref "U1") (pin "G3") (pinfunction "GPIO33_G3") (pintype "bidirectional"))
      (node (ref "U6") (pin "17") (pinfunction "SA0/H_MOSI_17") (pintype "input"))
    )
    (net (code "9") (name "AP4_GP13{slash}TT_9DOF_~{BOOT}") (class "Default")
      (node (ref "R20") (pin "1") (pinfunction "1_1") (pintype "passive"))
      (node (ref "U1") (pin "D5") (pinfunction "GPIO13_D5") (pintype "bidirectional"))
      (node (ref "U6") (pin "4") (pinfunction "~{BOOT}_4") (pintype "input"))
    )
    (net (code "10") (name "AP4_GP14{slash}TT_~{DW_SPI_CS}") (class "Default")
      (node (ref "U1") (pin "D6") (pinfunction "GPIO14_D6") (pintype "bidirectional"))
      (node (ref "U2") (pin "B5") (pinfunction "~{SPICS}_B5") (pintype "bidirectional"))
    )
    (net (code "11") (name "AP4_GP17{slash}TT_9DOF_H_~{INT}") (class "Default")
      (node (ref "U1") (pin "D4") (pinfunction "GPIO17_D4") (pintype "bidirectional"))
      (node (ref "U6") (pin "14") (pinfunction "H_INTN_14") (pintype "output"))
    )
    (net (code "12") (name "AP4_GP18{slash}TT_BATIN") (class "Default")
      (node (ref "C27") (pin "1") (pinfunction "1_1") (pintype "bidirectional"))
      (node (ref "R30") (pin "2") (pinfunction "2_2") (pintype "passive"))
      (node (ref "R31") (pin "1") (pinfunction "1_1") (pintype "passive"))
      (node (ref "U1") (pin "D3") (pinfunction "GPIO18_D3") (pintype "bidirectional"))
    )
    (net (code "13") (name "AP4_GP24{slash}TT_RFSW_V1") (class "Default")
      (node (ref "CX2") (pin "1") (pinfunction "1_1") (pintype "bidirectional"))
      (node (ref "S2") (pin "4") (pinfunction "V1_4") (pintype "input"))
      (node (ref "U1") (pin "E2") (pinfunction "GPIO24_E2") (pintype "bidirectional"))
    )
    (net (code "14") (name "AP4_GP25{slash}TT_RFSW_V2") (class "Default")
      (node (ref "CX1") (pin "1") (pinfunction "1_1") (pintype "bidirectional"))
      (node (ref "S2") (pin "5") (pinfunction "V2_5") (pintype "input"))
      (node (ref "U1") (pin "K5") (pinfunction "GPIO25_K5") (pintype "bidirectional"))
    )
    (net (code "15") (name "AP4_GP26{slash}TT_DW_WAKEUP") (class "Default")
      (node (ref "U1") (pin "L5") (pinfunction "GPIO26_L5") (pintype "bidirectional"))
      (node (ref "U2") (pin "B9") (pinfunction "WAKEUP_B9") (pintype "bidirectional"))
    )
    (net (code "16") (name "AP4_GP27{slash}TT_DW_IRQ") (class "Default")
      (node (ref "R24") (pin "2") (pinfunction "2_2") (pintype "passive"))
      (node (ref "U1") (pin "M5") (pinfunction "GPIO27_M5") (pintype "bidirectional"))
      (node (ref "U2") (pin "B1") (pinfunction "IRQ/GPIO8_B1") (pintype "bidirectional"))
    )
    (net (code "17") (name "AP4_GP30{slash}TT_FLASH_~{WP}") (class "Default")
      (node (ref "U1") (pin "G4") (pinfunction "GPIO30_G4") (pintype "bidirectional"))
      (node (ref "U5") (pin "3") (pinfunction "~{WP}_3") (pintype "bidirectional"))
    )
    (net (code "18") (name "AP4_GP31{slash}TT_DW_SPI_CLK") (class "Default")
      (node (ref "U1") (pin "E8") (pinfunction "GPIO8_E8") (pintype "bidirectional"))
      (node (ref "U2") (pin "A8") (pinfunction "SPICLK_A8") (pintype "bidirectional"))
    )
    (net (code "19") (name "AP4_GP32{slash}TT_DW_SPI_IO0") (class "Default")
      (node (ref "U1") (pin "E7") (pinfunction "GPIO9_E7") (pintype "bidirectional"))
      (node (ref "U2") (pin "B7") (pinfunction "SPICDI(MOSI)_B7") (pintype "bidirectional"))
    )
    (net (code "20") (name "AP4_GP33{slash}TT_DW_SPI_IO1") (class "Default")
      (node (ref "U1") (pin "E6") (pinfunction "GPIO10_E6") (pintype "bidirectional"))
      (node (ref "U2") (pin "A6") (pinfunction "SPICDO(MISO)_A6") (pintype "bidirectional"))
    )
    (net (code "21") (name "AP4_GP47{slash}TT_FLASH_SCK") (class "Default")
      (node (ref "U1") (pin "F1") (pinfunction "GPIO47_F1") (pintype "bidirectional"))
      (node (ref "U5") (pin "6") (pinfunction "CLK_6") (pintype "input"))
    )
    (net (code "22") (name "AP4_GP48{slash}TT_FLASH_PDI_IO0") (class "Default")
      (node (ref "U1") (pin "E1") (pinfunction "GPIO48_E1") (pintype "bidirectional"))
      (node (ref "U5") (pin "5") (pinfunction "DI_5") (pintype "bidirectional"))
    )
    (net (code "23") (name "AP4_GP49{slash}TT_FLASH_PDO_IO1") (class "Default")
      (node (ref "U1") (pin "D1") (pinfunction "GPIO49_D1") (pintype "bidirectional"))
      (node (ref "U5") (pin "2") (pinfunction "DO_2") (pintype "bidirectional"))
    )
    (net (code "24") (name "AP4_GP50{slash}TT_~{DW_RESET}") (class "Default")
      (node (ref "U1") (pin "A9") (pinfunction "GPIO50_A9") (pintype "bidirectional"))
      (node (ref "U2") (pin "A10") (pinfunction "~{RST}_A10") (pintype "bidirectional"))
    )
    (net (code "25") (name "AP4_GP51{slash}LED1_GREEN") (class "Default")
      (node (ref "R2") (pin "2") (pinfunction "2_2") (pintype "passive"))
      (node (ref "U1") (pin "B9") (pinfunction "GPIO51_B9") (pintype "bidirectional"))
    )
    (net (code "26") (name "AP4_GP53{slash}LED1_RED") (class "Default")
      (node (ref "R5") (pin "2") (pinfunction "2_2") (pintype "passive"))
      (node (ref "U1") (pin "C9") (pinfunction "GPIO53_C9") (pintype "bidirectional"))
    )
    (net (code "27") (name "AP4_GP55{slash}TT_BUZZER_GATE") (class "Default")
      (node (ref "Q2") (pin "G") (pinfunction "G_G") (pintype "passive"))
      (node (ref "R25") (pin "1") (pinfunction "1_1") (pintype "passive"))
      (node (ref "U1") (pin "D9") (pinfunction "GPIO55_D9") (pintype "bidirectional"))
    )
    (net (code "28") (name "AP4_GP58{slash}TT_~{CHG}") (class "Default")
      (node (ref "U1") (pin "J7") (pinfunction "GPIO58_J7") (pintype "bidirectional"))
      (node (ref "U3") (pin "8") (pinfunction "~{CHG}_8") (pintype "bidirectional"))
      (node (ref "U4") (pin "7") (pinfunction "~{CHG}_7") (pintype "bidirectional"))
    )
    (net (code "29") (name "AP4_GP60{slash}TT_~{PG}") (class "Default")
      (node (ref "U1") (pin "K8") (pinfunction "GPIO60_K8") (pintype "bidirectional"))
      (node (ref "U3") (pin "5") (pinfunction "~{PG}_5") (pintype "bidirectional"))
    )
    (net (code "30") (name "AP4_GP63{slash}TT_9DOF_PS0{slash}WAKE") (class "Default")
      (node (ref "U1") (pin "M6") (pinfunction "GPIO63_M6") (pintype "bidirectional"))
      (node (ref "U6") (pin "6") (pinfunction "PS0/WAKE_6") (pintype "input"))
    )
    (net (code "31") (name "AP4_GP65{slash}TT_9DOF_~{RESET}") (class "Default")
      (node (ref "RX8") (pin "1") (pinfunction "1_1") (pintype "passive"))
      (node (ref "U1") (pin "A7") (pinfunction "GPIO65_A7") (pintype "bidirectional"))
      (node (ref "U6") (pin "11") (pinfunction "~{RESET}_11") (pintype "input"))
    )
    (net (code "32") (name "AP4_GP66{slash}TT_QI_TS_CTRL") (class "Default")
      (node (ref "C30") (pin "1") (pinfunction "1_1") (pintype "bidirectional"))
      (node (ref "RT1") (pin "2") (pinfunction "2_2") (pintype "passive"))
      (node (ref "U1") (pin "A8") (pinfunction "GPIO66_A8") (pintype "bidirectional"))
      (node (ref "U4") (pin "13") (pinfunction "TS/CTRL_13") (pintype "bidirectional"))
    )
    (net (code "33") (name "AP4_GP69{slash}TT_FLASH_~{CS}") (class "Default")
      (node (ref "R21") (pin "1") (pinfunction "1_1") (pintype "passive"))
      (node (ref "U1") (pin "B8") (pinfunction "GPIO69_B8") (pintype "bidirectional"))
      (node (ref "U5") (pin "1") (pinfunction "~{CS}_1") (pintype "input"))
    )
    (net (code "34") (name "AP4_GP72{slash}TT_9DOF_H_~{CS}") (class "Default")
      (node (ref "U1") (pin "C8") (pinfunction "GPIO72_C8") (pintype "bidirectional"))
      (node (ref "U6") (pin "18") (pinfunction "H_~{CS}_18") (pintype "input"))
    )
    (net (code "35") (name "AP4_GP79{slash}LED2_RED") (class "Default")
      (node (ref "R4") (pin "2") (pinfunction "2_2") (pintype "passive"))
      (node (ref "U1") (pin "M11") (pinfunction "GPIO79_M11") (pintype "bidirectional"))
    )
    (net (code "36") (name "AP4_GP80{slash}SWTRACE0") (class "Default")
      (node (ref "J3") (pin "2") (pinfunction "SWDIO_2") (pintype "bidirectional"))
      (node (ref "J3") (pin "B2") (pinfunction "SWDIO_B2") (pintype "bidirectional"))
      (node (ref "U1") (pin "K10") (pinfunction "GPIO80_K10") (pintype "bidirectional"))
    )
    (net (code "37") (name "AP4_GP81{slash}SWTRACE1") (class "Default")
      (node (ref "J3") (pin "4") (pinfunction "SWDCLK_4") (pintype "bidirectional"))
      (node (ref "J3") (pin "B4") (pinfunction "SWDCLK_B4") (pintype "bidirectional"))
      (node (ref "U1") (pin "L10") (pinfunction "GPIO81_L10") (pintype "bidirectional"))
    )
    (net (code "38") (name "AP4_GP82{slash}SWTRACE2") (class "Default")
      (node (ref "J3") (pin "6") (pinfunction "SWO_6") (pintype "bidirectional"))
      (node (ref "J3") (pin "B6") (pinfunction "SWO_B6") (pintype "bidirectional"))
      (node (ref "U1") (pin "L9") (pinfunction "GPIO82_L9") (pintype "bidirectional"))
    )
    (net (code "39") (name "AP4_GP83{slash}SWTRACE3") (class "Default")
      (node (ref "J3") (pin "3") (pinfunction "~{RESET}_3") (pintype "bidirectional"))
      (node (ref "J3") (pin "B3") (pinfunction "~{RESET}_B3") (pintype "bidirectional"))
      (node (ref "U1") (pin "K9") (pinfunction "GPIO83_K9") (pintype "bidirectional"))
    )
    (net (code "40") (name "AP4_GP88{slash}LED2_YLW") (class "Default")
      (node (ref "R3") (pin "2") (pinfunction "2_2") (pintype "passive"))
      (node (ref "U1") (pin "F9") (pinfunction "GPIO88_F9") (pintype "bidirectional"))
    )
    (net (code "41") (name "AP4_SWDCLK") (class "Default")
      (node (ref "J2") (pin "4") (pinfunction "SWDCLK_4") (pintype "bidirectional"))
      (node (ref "J2") (pin "B4") (pinfunction "SWDCLK_B4") (pintype "bidirectional"))
      (node (ref "U1") (pin "K3") (pinfunction "GPIO20_K3") (pintype "bidirectional"))
    )
    (net (code "42") (name "AP4_SWDIO") (class "Default")
      (node (ref "J2") (pin "2") (pinfunction "SWDIO_2") (pintype "bidirectional"))
      (node (ref "J2") (pin "B2") (pinfunction "SWDIO_B2") (pintype "bidirectional"))
      (node (ref "U1") (pin "J3") (pinfunction "GPIO21_J3") (pintype "bidirectional"))
    )
    (net (code "43") (name "AP4_SWO") (class "Default")
      (node (ref "J2") (pin "6") (pinfunction "SWO_6") (pintype "bidirectional"))
      (node (ref "J2") (pin "B6") (pinfunction "SWO_B6") (pintype "bidirectional"))
      (node (ref "U1") (pin "L4") (pinfunction "GPIO3_L4") (pintype "bidirectional"))
    )
    (net (code "44") (name "AP4_SWTRACECLK") (class "Default")
      (node (ref "J3") (pin "1") (pinfunction "VTREF_1") (pintype "bidirectional"))
      (node (ref "J3") (pin "B1") (pinfunction "VTREF_B1") (pintype "bidirectional"))
      (node (ref "U1") (pin "F12") (pinfunction "GPIO38_F12") (pintype "bidirectional"))
    )
    (net (code "45") (name "AP4_USB0_N") (class "Default")
      (node (ref "U1") (pin "M8") (pinfunction "USB0PN_M8") (pintype "bidirectional"))
    )
    (net (code "46") (name "AP4_USB0_P") (class "Default")
      (node (ref "U1") (pin "M7") (pinfunction "USB0PP_M7") (pintype "bidirectional"))
    )
    (net (code "47") (name "AP4_VDDBH") (class "Default")
      (node (ref "C69") (pin "1") (pinfunction "1_1") (pintype "bidirectional"))
      (node (ref "L6") (pin "2") (pinfunction "2_2") (pintype "bidirectional"))
      (node (ref "RZ9") (pin "1") (pinfunction "1_1") (pintype "passive"))
      (node (ref "TP8") (pin "P$1") (pinfunction "TESTPOINT_P$1") (pintype "bidirectional"))
      (node (ref "U1") (pin "G12") (pinfunction "VDDBH--BLE_BUCK_VOUT_G12") (pintype "bidirectional"))
    )
    (net (code "48") (name "AP4_VDDBH_RF") (class "Default")
      (node (ref "C93") (pin "P$1") (pinfunction "1_P$1") (pintype "bidirectional"))
      (node (ref "RZ9") (pin "2") (pinfunction "2_2") (pintype "passive"))
      (node (ref "U1") (pin "J1") (pinfunction "VDDBH_RF--BLE_BUCK_RF_VOUT_J1") (pintype "bidirectional"))
    )
    (net (code "49") (name "AP4_VDDF") (class "Default")
      (node (ref "C61") (pin "P$1") (pinfunction "1_P$1") (pintype "bidirectional"))
      (node (ref "C75") (pin "P$1") (pinfunction "1_P$1") (pintype "bidirectional"))
      (node (ref "TP10") (pin "P$1") (pinfunction "TESTPOINT_P$1") (pintype "bidirectional"))
      (node (ref "U1") (pin "C2") (pinfunction "VDDF-MEM_C2") (pintype "bidirectional"))
    )
    (net (code "50") (name "AP4_VDDMIPI_1P8") (class "Default")
      (node (ref "C70") (pin "P$1") (pinfunction "1_P$1") (pintype "bidirectional"))
      (node (ref "RZ8") (pin "1") (pinfunction "1_1") (pintype "passive"))
      (node (ref "U1") (pin "H10") (pinfunction "VDD18-MIPI_H10") (pintype "bidirectional"))
    )
    (net (code "51") (name "AP4_VDDUSB_0P9") (class "Default")
      (node (ref "C73") (pin "P$1") (pinfunction "1_P$1") (pintype "bidirectional"))
      (node (ref "RZ6") (pin "1") (pinfunction "1_1") (pintype "passive"))
      (node (ref "U1") (pin "L7") (pinfunction "VDDUSB0P9_L7") (pintype "bidirectional"))
    )
    (net (code "52") (name "AP4_VDDUSB_3P3") (class "Default")
      (node (ref "C74") (pin "P$1") (pinfunction "1_P$1") (pintype "bidirectional"))
      (node (ref "RZ7") (pin "1") (pinfunction "1_1") (pintype "passive"))
      (node (ref "U1") (pin "K7") (pinfunction "VDDUSB33_K7") (pintype "bidirectional"))
    )
    (net (code "53") (name "AP4_~{RESET}") (class "Default")
      (node (ref "C76") (pin "1") (pinfunction "1_1") (pintype "passive"))
      (node (ref "D3") (pin "1") (pinfunction "C_1") (pintype "passive"))
      (node (ref "J2") (pin "3") (pinfunction "~{RESET}_3") (pintype "bidirectional"))
      (node (ref "J2") (pin "B3") (pinfunction "~{RESET}_B3") (pintype "bidirectional"))
      (node (ref "U1") (pin "A6") (pinfunction "~{RST}_A6") (pintype "input"))
    )
    (net (code "54") (name "BATT_THERM") (class "Default")
      (node (ref "J4") (pin "2") (pinfunction "2_2") (pintype "bidirectional"))
      (node (ref "J4") (pin "2SUPP") (pinfunction "2_2SUPP") (pintype "bidirectional"))
      (node (ref "JP2") (pin "3") (pinfunction "3_3") (pintype "passive"))
    )
    (net (code "55") (name "BATT_TS") (class "Default")
      (node (ref "JP2") (pin "2") (pinfunction "2_2") (pintype "passive"))
      (node (ref "U3") (pin "9") (pinfunction "TS_9") (pintype "bidirectional"))
    )
    (net (code "56") (name "BNO_ENV_SCL") (class "Default")
      (node (ref "R12") (pin "1") (pinfunction "1_1") (pintype "passive"))
      (node (ref "U6") (pin "15") (pinfunction "ENV_SCL_15") (pintype "bidirectional"))
    )
    (net (code "57") (name "BNO_ENV_SDA") (class "Default")
      (node (ref "R16") (pin "1") (pinfunction "1_1") (pintype "passive"))
      (node (ref "U6") (pin "16") (pinfunction "ENV_SDA_16") (pintype "bidirectional"))
    )
    (net (code "58") (name "D+") (class "Default")
      (node (ref "XJ1") (pin "A6") (pinfunction "DP1_A6") (pintype "bidirectional"))
      (node (ref "XJ1") (pin "B6") (pinfunction "DP2_B6") (pintype "bidirectional"))
    )
    (net (code "59") (name "D-") (class "Default")
      (node (ref "XJ1") (pin "A7") (pinfunction "DN1_A7") (pintype "bidirectional"))
      (node (ref "XJ1") (pin "B7") (pinfunction "DN2_B7") (pintype "bidirectional"))
    )
    (net (code "60") (name "DW_EXTON") (class "Default")
      (node (ref "JP12") (pin "2") (pinfunction "2_2") (pintype "passive"))
      (node (ref "RX1") (pin "2") (pinfunction "2_2") (pintype "passive"))
      (node (ref "S3") (pin "2") (pinfunction "CTL_2") (pintype "bidirectional"))
      (node (ref "S3") (pin "3") (pinfunction "CTL_3") (pintype "bidirectional"))
      (node (ref "VR3") (pin "3") (pinfunction "EN_3") (pintype "input"))
    )
    (net (code "61") (name "DW_EXTON_RAW") (class "Default")
      (node (ref "JP12") (pin "3") (pinfunction "3_3") (pintype "passive"))
      (node (ref "U2") (pin "A12") (pinfunction "EXTON_A12") (pintype "bidirectional"))
    )
    (net (code "62") (name "DW_GPIO6{slash}EXTRXE") (class "Default")
      (node (ref "JP3") (pin "3") (pinfunction "3_3") (pintype "passive"))
      (node (ref "TP6") (pin "P$1") (pinfunction "TESTPOINT_P$1") (pintype "bidirectional"))
      (node (ref "U2") (pin "C4") (pinfunction "GPIO6/EXTRXE/SPIPHA_C4") (pintype "bidirectional"))
    )
    (net (code "63") (name "DW_SYNC") (class "Default")
      (node (ref "TP7") (pin "P$1") (pinfunction "TESTPOINT_P$1") (pintype "bidirectional"))
      (node (ref "U2") (pin "G2") (pinfunction "GPIO7/SYNC_G2") (pintype "bidirectional"))
    )
    (net (code "64") (name "DW_VDD2_SUP") (class "Default")
      (node (ref "C13") (pin "P$1") (pinfunction "P$1_P$1") (pintype "bidirectional"))
      (node (ref "C24") (pin "P$1") (pinfunction "P$1_P$1") (pintype "bidirectional"))
      (node (ref "C55") (pin "P$1") (pinfunction "P$1_P$1") (pintype "bidirectional"))
      (node (ref "FB1") (pin "P$1") (pinfunction "P$1_P$1") (pintype "bidirectional"))
      (node (ref "RZ1") (pin "2") (pinfunction "2_2") (pintype "passive"))
      (node (ref "U2") (pin "B15") (pinfunction "VDD2B_B15") (pintype "bidirectional"))
    )
    (net (code "65") (name "DW_VDD3_SUP") (class "Default")
      (node (ref "C14") (pin "P$2") (pinfunction "P$2_P$2") (pintype "bidirectional"))
      (node (ref "C22") (pin "P$2") (pinfunction "P$2_P$2") (pintype "bidirectional"))
      (node (ref "C54") (pin "P$2") (pinfunction "P$2_P$2") (pintype "bidirectional"))
      (node (ref "RZ2") (pin "2") (pinfunction "2_2") (pintype "passive"))
      (node (ref "U2") (pin "D15") (pinfunction "VDD3_D15") (pintype "bidirectional"))
    )
    (net (code "66") (name "GND") (class "Default")
      (node (ref "C11") (pin "P$2") (pinfunction "P$2_P$2") (pintype "bidirectional"))
      (node (ref "C12") (pin "P$2") (pinfunction "P$2_P$2") (pintype "bidirectional"))
      (node (ref "C13") (pin "P$2") (pinfunction "P$2_P$2") (pintype "bidirectional"))
      (node (ref "C14") (pin "P$1") (pinfunction "P$1_P$1") (pintype "bidirectional"))
      (node (ref "C22") (pin "P$1") (pinfunction "P$1_P$1") (pintype "bidirectional"))
      (node (ref "C23") (pin "2") (pinfunction "2_2") (pintype "bidirectional"))
      (node (ref "C24") (pin "P$2") (pinfunction "P$2_P$2") (pintype "bidirectional"))
      (node (ref "C25") (pin "2") (pinfunction "2_2") (pintype "bidirectional"))
      (node (ref "C26") (pin "2") (pinfunction "2_2") (pintype "bidirectional"))
      (node (ref "C27") (pin "2") (pinfunction "2_2") (pintype "bidirectional"))
      (node (ref "C28") (pin "2") (pinfunction "2_2") (pintype "bidirectional"))
      (node (ref "C29") (pin "2") (pinfunction "2_2") (pintype "bidirectional"))
      (node (ref "C3") (pin "P$2") (pinfunction "P$2_P$2") (pintype "bidirectional"))
      (node (ref "C30") (pin "2") (pinfunction "2_2") (pintype "bidirectional"))
      (node (ref "C31") (pin "2") (pinfunction "2_2") (pintype "bidirectional"))
      (node (ref "C32") (pin "2") (pinfunction "2_2") (pintype "bidirectional"))
      (node (ref "C33") (pin "2") (pinfunction "2_2") (pintype "bidirectional"))
      (node (ref "C34") (pin "2") (pinfunction "2_2") (pintype "bidirectional"))
      (node (ref "C35") (pin "2") (pinfunction "2_2") (pintype "bidirectional"))
      (node (ref "C36") (pin "2") (pinfunction "2_2") (pintype "bidirectional"))
      (node (ref "C37") (pin "P$1") (pinfunction "P$1_P$1") (pintype "bidirectional"))
      (node (ref "C4") (pin "P$2") (pinfunction "P$2_P$2") (pintype "bidirectional"))
      (node (ref "C40") (pin "1") (pinfunction "1_1") (pintype "bidirectional"))
      (node (ref "C41") (pin "2") (pinfunction "2_2") (pintype "bidirectional"))
      (node (ref "C42") (pin "2") (pinfunction "2_2") (pintype "bidirectional"))
      (node (ref "C43") (pin "P$2") (pinfunction "P$2_P$2") (pintype "bidirectional"))
      (node (ref "C44") (pin "2") (pinfunction "2_2") (pintype "bidirectional"))
      (node (ref "C45") (pin "1") (pinfunction "1_1") (pintype "bidirectional"))
      (node (ref "C46") (pin "2") (pinfunction "2_2") (pintype "bidirectional"))
      (node (ref "C47") (pin "1") (pinfunction "1_1") (pintype "bidirectional"))
      (node (ref "C48") (pin "2") (pinfunction "2_2") (pintype "bidirectional"))
      (node (ref "C49") (pin "2") (pinfunction "2_2") (pintype "bidirectional"))
      (node (ref "C5") (pin "P$1") (pinfunction "1_P$1") (pintype "bidirectional"))
      (node (ref "C50") (pin "1") (pinfunction "1_1") (pintype "bidirectional"))
      (node (ref "C53") (pin "2") (pinfunction "2_2") (pintype "bidirectional"))
      (node (ref "C54") (pin "P$1") (pinfunction "P$1_P$1") (pintype "bidirectional"))
      (node (ref "C55") (pin "P$2") (pinfunction "P$2_P$2") (pintype "bidirectional"))
      (node (ref "C56") (pin "2") (pinfunction "2_2") (pintype "bidirectional"))
      (node (ref "C57") (pin "2") (pinfunction "2_2") (pintype "bidirectional"))
      (node (ref "C58") (pin "P$2") (pinfunction "2_P$2") (pintype "bidirectional"))
      (node (ref "C59") (pin "P$2") (pinfunction "2_P$2") (pintype "bidirectional"))
      (node (ref "C6") (pin "P$1") (pinfunction "1_P$1") (pintype "bidirectional"))
      (node (ref "C60") (pin "P$2") (pinfunction "2_P$2") (pintype "bidirectional"))
      (node (ref "C61") (pin "P$2") (pinfunction "2_P$2") (pintype "bidirectional"))
      (node (ref "C62") (pin "P$2") (pinfunction "2_P$2") (pintype "bidirectional"))
      (node (ref "C63") (pin "P$2") (pinfunction "2_P$2") (pintype "bidirectional"))
      (node (ref "C64") (pin "P$2") (pinfunction "2_P$2") (pintype "bidirectional"))
      (node (ref "C65") (pin "P$2") (pinfunction "2_P$2") (pintype "bidirectional"))
      (node (ref "C66") (pin "P$2") (pinfunction "2_P$2") (pintype "bidirectional"))
      (node (ref "C67") (pin "P$2") (pinfunction "2_P$2") (pintype "bidirectional"))
      (node (ref "C69") (pin "2") (pinfunction "2_2") (pintype "bidirectional"))
      (node (ref "C70") (pin "P$2") (pinfunction "2_P$2") (pintype "bidirectional"))
      (node (ref "C71") (pin "P$1") (pinfunction "1_P$1") (pintype "bidirectional"))
      (node (ref "C72") (pin "P$2") (pinfunction "2_P$2") (pintype "bidirectional"))
      (node (ref "C73") (pin "P$2") (pinfunction "2_P$2") (pintype "bidirectional"))
      (node (ref "C74") (pin "P$2") (pinfunction "2_P$2") (pintype "bidirectional"))
      (node (ref "C76") (pin "2") (pinfunction "2_2") (pintype "passive"))
      (node (ref "C77") (pin "P$2") (pinfunction "2_P$2") (pintype "bidirectional"))
      (node (ref "C78") (pin "P$2") (pinfunction "2_P$2") (pintype "bidirectional"))
      (node (ref "C79") (pin "P$1") (pinfunction "1_P$1") (pintype "bidirectional"))
      (node (ref "C80") (pin "2") (pinfunction "2_2") (pintype "passive"))
      (node (ref "C81") (pin "2") (pinfunction "2_2") (pintype "passive"))
      (node (ref "C90") (pin "P$2") (pinfunction "2_P$2") (pintype "bidirectional"))
      (node (ref "C91") (pin "P$2") (pinfunction "2_P$2") (pintype "bidirectional"))
      (node (ref "CX1") (pin "2") (pinfunction "2_2") (pintype "bidirectional"))
      (node (ref "CX2") (pin "2") (pinfunction "2_2") (pintype "bidirectional"))
      (node (ref "CX3") (pin "2") (pinfunction "2_2") (pintype "passive"))
      (node (ref "CX4") (pin "2") (pinfunction "2_2") (pintype "passive"))
      (node (ref "D3") (pin "2") (pinfunction "A_2") (pintype "passive"))
      (node (ref "J2") (pin "5") (pinfunction "GND_5") (pintype "bidirectional"))
      (node (ref "J2") (pin "B5") (pinfunction "GND_B5") (pintype "bidirectional"))
      (node (ref "J3") (pin "5") (pinfunction "GND_5") (pintype "bidirectional"))
      (node (ref "J3") (pin "B5") (pinfunction "GND_B5") (pintype "bidirectional"))
      (node (ref "J4") (pin "1") (pinfunction "1_1") (pintype "bidirectional"))
      (node (ref "J4") (pin "1SUPP") (pinfunction "1_1SUPP") (pintype "bidirectional"))
      (node (ref "JP3") (pin "1") (pinfunction "1_1") (pintype "passive"))
      (node (ref "JP9") (pin "2") (pinfunction "2_2") (pintype "passive"))
      (node (ref "Q2") (pin "S") (pinfunction "S_S") (pintype "passive"))
      (node (ref "R1") (pin "2") (pinfunction "2_2") (pintype "passive"))
      (node (ref "R14") (pin "1") (pinfunction "1_1") (pintype "passive"))
      (node (ref "R15") (pin "1") (pinfunction "1_1") (pintype "passive"))
      (node (ref "R24") (pin "1") (pinfunction "1_1") (pintype "passive"))
      (node (ref "R25") (pin "2") (pinfunction "2_2") (pintype "passive"))
      (node (ref "R26") (pin "1") (pinfunction "1_1") (pintype "passive"))
      (node (ref "R27") (pin "1") (pinfunction "1_1") (pintype "passive"))
      (node (ref "R30") (pin "1") (pinfunction "1_1") (pintype "passive"))
      (node (ref "R6") (pin "2") (pinfunction "2_2") (pintype "passive"))
      (node (ref "RX7") (pin "1") (pinfunction "1_1") (pintype "passive"))
      (node (ref "RX9") (pin "1") (pinfunction "1_1") (pintype "passive"))
      (node (ref "RZ6") (pin "2") (pinfunction "2_2") (pintype "passive"))
      (node (ref "RZ7") (pin "2") (pinfunction "2_2") (pintype "passive"))
      (node (ref "RZ8") (pin "2") (pinfunction "2_2") (pintype "passive"))
      (node (ref "S2") (pin "10") (pinfunction "GND_10") (pintype "bidirectional"))
      (node (ref "S2") (pin "12") (pinfunction "GND_12") (pintype "bidirectional"))
      (node (ref "S2") (pin "2") (pinfunction "GND_2") (pintype "bidirectional"))
      (node (ref "S2") (pin "7") (pinfunction "GND_7") (pintype "bidirectional"))
      (node (ref "S2") (pin "8") (pinfunction "GND_8") (pintype "bidirectional"))
      (node (ref "S2") (pin "PAD") (pinfunction "GND_PAD") (pintype "bidirectional"))
      (node (ref "S3") (pin "6") (pinfunction "GND_6") (pintype "bidirectional"))
      (node (ref "S3") (pin "7") (pinfunction "GND_7") (pintype "bidirectional"))
      (node (ref "S3") (pin "PAD") (pinfunction "GND_PAD") (pintype "bidirectional"))
      (node (ref "S4") (pin "G1") (pinfunction "GND_G1") (pintype "bidirectional"))
      (node (ref "S4") (pin "G2") (pinfunction "GND_G2") (pintype "bidirectional"))
      (node (ref "U1") (pin "B12") (pinfunction "VSSAUDA_B12") (pintype "bidirectional"))
      (node (ref "U1") (pin "B2") (pinfunction "VSSP-BUCK_REGS_GND_B2") (pintype "bidirectional"))
      (node (ref "U1") (pin "B5") (pinfunction "VSSA-ANALOG_GND_B5") (pintype "bidirectional"))
      (node (ref "U1") (pin "D2") (pinfunction "VSS-DGND_FOR_VDDF_AND_PADS_D2") (pintype "bidirectional"))
      (node (ref "U1") (pin "E12") (pinfunction "VSSAUDD_E12") (pintype "bidirectional"))
      (node (ref "U1") (pin "H1") (pinfunction "VSSB-BLE_UNREG_GND_H1") (pintype "bidirectional"))
      (node (ref "U1") (pin "J10") (pinfunction "VSS18-MIPI_J10") (pintype "bidirectional"))
      (node (ref "U1") (pin "L1") (pinfunction "VSSVCO-BLECORE_GND_FOR_VCO_L1") (pintype "bidirectional"))
      (node (ref "U1") (pin "L2") (pinfunction "VSSS-HVSIMOBUCK_GND_L2") (pintype "bidirectional"))
      (node (ref "U1") (pin "L8") (pinfunction "VSSAUSB_L8") (pintype "bidirectional"))
      (node (ref "U2") (pin "A14") (pinfunction "VSS1_A14") (pintype "bidirectional"))
      (node (ref "U2") (pin "A2") (pinfunction "VSS_A2") (pintype "bidirectional"))
      (node (ref "U2") (pin "B11") (pinfunction "VSS1_B11") (pintype "bidirectional"))
      (node (ref "U2") (pin "B3") (pinfunction "VSS_B3") (pintype "bidirectional"))
      (node (ref "U2") (pin "C10") (pinfunction "VSS1_C10") (pintype "bidirectional"))
      (node (ref "U2") (pin "C12") (pinfunction "VSS3_C12") (pintype "bidirectional"))
      (node (ref "U2") (pin "C6") (pinfunction "VSS_C6") (pintype "bidirectional"))
      (node (ref "U2") (pin "C8") (pinfunction "VSS1_C8") (pintype "bidirectional"))
      (node (ref "U2") (pin "D11") (pinfunction "VSS2_D11") (pintype "bidirectional"))
      (node (ref "U2") (pin "D13") (pinfunction "VSS3_D13") (pintype "bidirectional"))
      (node (ref "U2") (pin "D5") (pinfunction "VSS_D5") (pintype "bidirectional"))
      (node (ref "U2") (pin "D7") (pinfunction "VSS_D7") (pintype "bidirectional"))
      (node (ref "U2") (pin "D9") (pinfunction "VSS1_D9") (pintype "bidirectional"))
      (node (ref "U2") (pin "E10") (pinfunction "GND-RF_E10") (pintype "bidirectional"))
      (node (ref "U2") (pin "E12") (pinfunction "GND-RF_E12") (pintype "bidirectional"))
      (node (ref "U2") (pin "E14") (pinfunction "VSS2_E14") (pintype "bidirectional"))
      (node (ref "U2") (pin "E6") (pinfunction "GND-RF_E6") (pintype "bidirectional"))
      (node (ref "U2") (pin "F7") (pinfunction "GND-RF_F7") (pintype "bidirectional"))
      (node (ref "U2") (pin "F9") (pinfunction "GND-RF_F9") (pintype "bidirectional"))
      (node (ref "U2") (pin "G10") (pinfunction "GND-RF_G10") (pintype "bidirectional"))
      (node (ref "U2") (pin "G6") (pinfunction "GND-RF_G6") (pintype "bidirectional"))
      (node (ref "U2") (pin "H1") (pinfunction "GND-RF_H1") (pintype "bidirectional"))
      (node (ref "U2") (pin "H13") (pinfunction "GND-RF_H13") (pintype "bidirectional"))
      (node (ref "U2") (pin "H3") (pinfunction "GND-RF_H3") (pintype "bidirectional"))
      (node (ref "U2") (pin "H7") (pinfunction "GND-RF_H7") (pintype "bidirectional"))
      (node (ref "U2") (pin "H9") (pinfunction "GND-RF_H9") (pintype "bidirectional"))
      (node (ref "U3") (pin "3") (pinfunction "VSS_3") (pintype "bidirectional"))
      (node (ref "U3") (pin "7") (pinfunction "ISET2_7") (pintype "bidirectional"))
      (node (ref "U3") (pin "PAD") (pinfunction "VSS_PAD") (pintype "bidirectional"))
      (node (ref "U4") (pin "1") (pinfunction "PGND_1") (pintype "bidirectional"))
      (node (ref "U4") (pin "10") (pinfunction "EN1_10") (pintype "bidirectional"))
      (node (ref "U4") (pin "11") (pinfunction "EN2_11") (pintype "bidirectional"))
      (node (ref "U4") (pin "20") (pinfunction "PGND_20") (pintype "bidirectional"))
      (node (ref "U4") (pin "PAD") (pinfunction "PGND_PAD") (pintype "bidirectional"))
      (node (ref "U5") (pin "4") (pinfunction "GND_4") (pintype "bidirectional"))
      (node (ref "U6") (pin "10") (pinfunction "CLKSEL0_10") (pintype "output"))
      (node (ref "U6") (pin "2") (pinfunction "GND_2") (pintype "bidirectional"))
      (node (ref "U6") (pin "25") (pinfunction "GNDIO_25") (pintype "bidirectional"))
      (node (ref "U7") (pin "3") (pinfunction "GND_3") (pintype "bidirectional"))
      (node (ref "U7") (pin "4") (pinfunction "GND_4") (pintype "bidirectional"))
      (node (ref "U7") (pin "5") (pinfunction "GND_5") (pintype "bidirectional"))
      (node (ref "U7") (pin "7") (pinfunction "GND_7") (pintype "bidirectional"))
      (node (ref "U7") (pin "9") (pinfunction "GND_9") (pintype "bidirectional"))
      (node (ref "VR1") (pin "13") (pinfunction "GND2_13") (pintype "bidirectional"))
      (node (ref "VR1") (pin "3") (pinfunction "GND2_3") (pintype "bidirectional"))
      (node (ref "VR1") (pin "9") (pinfunction "GND1_9") (pintype "bidirectional"))
      (node (ref "VR2") (pin "2") (pinfunction "GND_2") (pintype "bidirectional"))
      (node (ref "VR2") (pin "PAD") (pinfunction "GND_PAD") (pintype "bidirectional"))
      (node (ref "VR3") (pin "2") (pinfunction "GND_2") (pintype "bidirectional"))
      (node (ref "VR3") (pin "PAD") (pinfunction "GND_PAD") (pintype "bidirectional"))
      (node (ref "X1") (pin "2") (pinfunction "GND_2") (pintype "bidirectional"))
      (node (ref "X1") (pin "4") (pinfunction "GND_4") (pintype "bidirectional"))
      (node (ref "X4") (pin "2") (pinfunction "GND_2") (pintype "bidirectional"))
      (node (ref "X4") (pin "4") (pinfunction "GND_4") (pintype "bidirectional"))
      (node (ref "XJ1") (pin "A1/B12") (pinfunction "GND_A1/B12") (pintype "power_in"))
      (node (ref "XJ1") (pin "B1/A12") (pinfunction "GND_B1/A12") (pintype "power_in"))
      (node (ref "XJ1") (pin "S1") (pinfunction "GND_S1") (pintype "power_in"))
      (node (ref "XJ1") (pin "S2") (pinfunction "GND_S2") (pintype "power_in"))
      (node (ref "XJ1") (pin "S3") (pinfunction "GND_S3") (pintype "power_in"))
      (node (ref "XJ1") (pin "S4") (pinfunction "GND_S4") (pintype "power_in"))
      (node (ref "XR16") (pin "2") (pinfunction "2_2") (pintype "passive"))
      (node (ref "XR17") (pin "2") (pinfunction "2_2") (pintype "passive"))
      (node (ref "XR19") (pin "1") (pinfunction "1_1") (pintype "passive"))
    )
    (net (code "67") (name "Net-(A4-ANTENNA)") (class "Default")
      (node (ref "A4") (pin "S1") (pinfunction "ANTENNA_S1") (pintype "bidirectional"))
      (node (ref "L8") (pin "2") (pinfunction "2_2") (pintype "passive"))
    )
    (net (code "68") (name "Net-(C1-Pad1)") (class "Default")
      (node (ref "C1") (pin "1") (pinfunction "1_1") (pintype "passive"))
      (node (ref "L7") (pin "2") (pinfunction "2_2") (pintype "passive"))
      (node (ref "L8") (pin "1") (pinfunction "1_1") (pintype "passive"))
    )
    (net (code "69") (name "Net-(C2-1)") (class "Default")
      (node (ref "C2") (pin "P$1") (pinfunction "1_P$1") (pintype "bidirectional"))
      (node (ref "U2") (pin "H11") (pinfunction "RF1_H11") (pintype "bidirectional"))
    )
    (net (code "70") (name "Net-(C2-2)") (class "Default")
      (node (ref "C2") (pin "P$2") (pinfunction "2_P$2") (pintype "bidirectional"))
      (node (ref "S2") (pin "11") (pinfunction "RFC_11") (pintype "bidirectional"))
    )
    (net (code "71") (name "Net-(C5-2)") (class "Default")
      (node (ref "C5") (pin "P$2") (pinfunction "2_P$2") (pintype "bidirectional"))
      (node (ref "U6") (pin "27") (pinfunction "XIN32_27") (pintype "bidirectional"))
      (node (ref "X2") (pin "2") (pinfunction "2_2") (pintype "bidirectional"))
    )
    (net (code "72") (name "Net-(C6-2)") (class "Default")
      (node (ref "C6") (pin "P$2") (pinfunction "2_P$2") (pintype "bidirectional"))
      (node (ref "U6") (pin "26") (pinfunction "XOUT32/CLKSEL1_26") (pintype "bidirectional"))
      (node (ref "X2") (pin "1") (pinfunction "1_1") (pintype "bidirectional"))
    )
    (net (code "73") (name "Net-(C7-2)") (class "Default")
      (node (ref "C7") (pin "P$2") (pinfunction "2_P$2") (pintype "bidirectional"))
      (node (ref "R26") (pin "2") (pinfunction "2_2") (pintype "passive"))
      (node (ref "R28") (pin "1") (pinfunction "1_1") (pintype "passive"))
      (node (ref "VR1") (pin "10") (pinfunction "FB2_10") (pintype "bidirectional"))
    )
    (net (code "74") (name "Net-(C8-1)") (class "Default")
      (node (ref "C8") (pin "P$1") (pinfunction "1_P$1") (pintype "bidirectional"))
      (node (ref "R27") (pin "2") (pinfunction "2_2") (pintype "passive"))
      (node (ref "R29") (pin "2") (pinfunction "2_2") (pintype "passive"))
      (node (ref "VR1") (pin "4") (pinfunction "FB1_4") (pintype "bidirectional"))
    )
    (net (code "75") (name "Net-(C58-1)") (class "Default")
      (node (ref "C58") (pin "P$1") (pinfunction "1_P$1") (pintype "bidirectional"))
      (node (ref "U1") (pin "C1") (pinfunction "VDDS-SRAM_HV_SUP_C1") (pintype "bidirectional"))
    )
    (net (code "76") (name "Net-(C59-1)") (class "Default")
      (node (ref "C59") (pin "P$1") (pinfunction "1_P$1") (pintype "bidirectional"))
      (node (ref "U1") (pin "A3") (pinfunction "VDDC-CORE_A3") (pintype "bidirectional"))
    )
    (net (code "77") (name "Net-(C60-1)") (class "Default")
      (node (ref "C60") (pin "P$1") (pinfunction "1_P$1") (pintype "bidirectional"))
      (node (ref "U1") (pin "B3") (pinfunction "VDDC_LV-CORE_LV_B3") (pintype "bidirectional"))
    )
    (net (code "78") (name "Net-(C71-2)") (class "Default")
      (node (ref "C71") (pin "P$2") (pinfunction "2_P$2") (pintype "bidirectional"))
      (node (ref "U1") (pin "B10") (pinfunction "LPMICBIAS_B10") (pintype "output"))
    )
    (net (code "79") (name "Net-(C78-1)") (class "Default")
      (node (ref "C78") (pin "P$1") (pinfunction "1_P$1") (pintype "bidirectional"))
      (node (ref "RZ11") (pin "1") (pinfunction "1_1") (pintype "passive"))
      (node (ref "VR2") (pin "1") (pinfunction "OUT_1") (pintype "power_in"))
    )
    (net (code "80") (name "Net-(C79-2)") (class "Default")
      (node (ref "C79") (pin "P$2") (pinfunction "2_P$2") (pintype "bidirectional"))
      (node (ref "U1") (pin "A12") (pinfunction "LPADC_VREF_A12") (pintype "bidirectional"))
    )
    (net (code "81") (name "Net-(C91-1)") (class "Default")
      (node (ref "C91") (pin "P$1") (pinfunction "1_P$1") (pintype "bidirectional"))
      (node (ref "RZ4") (pin "1") (pinfunction "1_1") (pintype "passive"))
      (node (ref "VR3") (pin "1") (pinfunction "OUT_1") (pintype "power_in"))
    )
    (net (code "82") (name "Net-(D1-PadA1)") (class "Default")
      (node (ref "D1") (pin "A1") (pinfunction "A1_A1") (pintype "bidirectional"))
      (node (ref "D1") (pin "A2") (pinfunction "A2_A2") (pintype "bidirectional"))
      (node (ref "D2") (pin "A1") (pinfunction "A1_A1") (pintype "bidirectional"))
      (node (ref "D2") (pin "A2") (pinfunction "A2_A2") (pintype "bidirectional"))
      (node (ref "JP1") (pin "1") (pinfunction "1_1") (pintype "passive"))
    )
    (net (code "83") (name "Net-(D1-PadC1)") (class "Default")
      (node (ref "D1") (pin "C1") (pinfunction "C1_C1") (pintype "bidirectional"))
      (node (ref "R5") (pin "1") (pinfunction "1_1") (pintype "passive"))
    )
    (net (code "84") (name "Net-(D1-PadC2)") (class "Default")
      (node (ref "D1") (pin "C2") (pinfunction "C2_C2") (pintype "bidirectional"))
      (node (ref "R2") (pin "1") (pinfunction "1_1") (pintype "passive"))
    )
    (net (code "85") (name "Net-(D2-PadC1)") (class "Default")
      (node (ref "D2") (pin "C1") (pinfunction "C1_C1") (pintype "bidirectional"))
      (node (ref "R4") (pin "1") (pinfunction "1_1") (pintype "passive"))
    )
    (net (code "86") (name "Net-(D2-PadC2)") (class "Default")
      (node (ref "D2") (pin "C2") (pinfunction "C2_C2") (pintype "bidirectional"))
      (node (ref "R3") (pin "1") (pinfunction "1_1") (pintype "passive"))
    )
    (net (code "87") (name "Net-(JP2-Pad1)") (class "Default")
      (node (ref "JP2") (pin "1") (pinfunction "1_1") (pintype "passive"))
      (node (ref "XR19") (pin "2") (pinfunction "2_2") (pintype "passive"))
    )
    (net (code "88") (name "Net-(L1-1)") (class "Default")
      (node (ref "L1") (pin "P$1") (pinfunction "1_P$1") (pintype "bidirectional"))
      (node (ref "VR1") (pin "2") (pinfunction "LX2_2") (pintype "bidirectional"))
    )
    (net (code "89") (name "Net-(L2-2)") (class "Default")
      (node (ref "L2") (pin "P$2") (pinfunction "2_P$2") (pintype "bidirectional"))
      (node (ref "VR1") (pin "8") (pinfunction "LX1_8") (pintype "bidirectional"))
    )
    (net (code "90") (name "Net-(L4-1)") (class "Default")
      (node (ref "C17") (pin "2") (pinfunction "2_2") (pintype "bidirectional"))
      (node (ref "C18") (pin "2") (pinfunction "2_2") (pintype "bidirectional"))
      (node (ref "C19") (pin "2") (pinfunction "2_2") (pintype "bidirectional"))
      (node (ref "L4") (pin "P$1") (pinfunction "1_P$1") (pintype "bidirectional"))
    )
    (net (code "91") (name "Net-(L4-2)") (class "Default")
      (node (ref "C10") (pin "2") (pinfunction "2_2") (pintype "bidirectional"))
      (node (ref "C16") (pin "2") (pinfunction "2_2") (pintype "bidirectional"))
      (node (ref "C21") (pin "2") (pinfunction "2_2") (pintype "bidirectional"))
      (node (ref "C39") (pin "2") (pinfunction "2_2") (pintype "bidirectional"))
      (node (ref "C9") (pin "2") (pinfunction "2_2") (pintype "bidirectional"))
      (node (ref "L4") (pin "P$2") (pinfunction "2_P$2") (pintype "bidirectional"))
      (node (ref "U4") (pin "19") (pinfunction "AC2_19") (pintype "bidirectional"))
    )
    (net (code "92") (name "Net-(L5-1)") (class "Default")
      (node (ref "L5") (pin "P$1") (pinfunction "1_P$1") (pintype "bidirectional"))
      (node (ref "U1") (pin "A1") (pinfunction "SIMOBUCK_SW_A1") (pintype "bidirectional"))
    )
    (net (code "93") (name "Net-(L5-2)") (class "Default")
      (node (ref "L5") (pin "P$2") (pinfunction "2_P$2") (pintype "bidirectional"))
      (node (ref "U1") (pin "A2") (pinfunction "SIMOBUCK_SWSEL_A2") (pintype "bidirectional"))
    )
    (net (code "94") (name "Net-(LS1-N)") (class "Default")
      (node (ref "D4") (pin "ANODE") (pinfunction "ANODE_ANODE") (pintype "bidirectional"))
      (node (ref "LS1") (pin "-") (pinfunction "N_-") (pintype "passive"))
      (node (ref "Q2") (pin "D") (pinfunction "D_D") (pintype "passive"))
    )
    (net (code "95") (name "Net-(R6-Pad1)") (class "Default")
      (node (ref "R6") (pin "1") (pinfunction "1_1") (pintype "passive"))
      (node (ref "R7") (pin "2") (pinfunction "2_2") (pintype "passive"))
    )
    (net (code "96") (name "Net-(R8-Pad2)") (class "Default")
      (node (ref "R8") (pin "2") (pinfunction "2_2") (pintype "passive"))
      (node (ref "R9") (pin "1") (pinfunction "1_1") (pintype "passive"))
    )
    (net (code "97") (name "Net-(R13-Pad1)") (class "Default")
      (node (ref "R13") (pin "1") (pinfunction "1_1") (pintype "passive"))
      (node (ref "R14") (pin "2") (pinfunction "2_2") (pintype "passive"))
    )
    (net (code "98") (name "Net-(R13-Pad2)") (class "Default")
      (node (ref "R13") (pin "2") (pinfunction "2_2") (pintype "passive"))
      (node (ref "RT1") (pin "1") (pinfunction "1_1") (pintype "passive"))
    )
    (net (code "99") (name "Net-(R18-Pad2)") (class "Default")
      (node (ref "R18") (pin "2") (pinfunction "2_2") (pintype "passive"))
      (node (ref "R23") (pin "1") (pinfunction "1_1") (pintype "passive"))
    )
    (net (code "100") (name "Net-(S3A-OUT)") (class "Default")
      (node (ref "C33") (pin "1") (pinfunction "1_1") (pintype "bidirectional"))
      (node (ref "RZ1") (pin "1") (pinfunction "1_1") (pintype "passive"))
      (node (ref "S3") (pin "8") (pinfunction "OUT_8") (pintype "bidirectional"))
    )
    (net (code "101") (name "Net-(S3B-OUT)") (class "Default")
      (node (ref "C25") (pin "1") (pinfunction "1_1") (pintype "bidirectional"))
      (node (ref "RZ2") (pin "1") (pinfunction "1_1") (pintype "passive"))
      (node (ref "S3") (pin "5") (pinfunction "OUT_5") (pintype "bidirectional"))
    )
    (net (code "102") (name "Net-(TP0-TESTPOINT)") (class "Default")
      (node (ref "TP0") (pin "P$1") (pinfunction "TESTPOINT_P$1") (pintype "bidirectional"))
      (node (ref "U2") (pin "C2") (pinfunction "GPIO0/RXOKLED_C2") (pintype "bidirectional"))
    )
    (net (code "103") (name "Net-(TP1-TESTPOINT)") (class "Default")
      (node (ref "TP1") (pin "P$1") (pinfunction "TESTPOINT_P$1") (pintype "bidirectional"))
      (node (ref "U2") (pin "D3") (pinfunction "GPIO1/SFDLED_D3") (pintype "bidirectional"))
    )
    (net (code "104") (name "Net-(TP2-TESTPOINT)") (class "Default")
      (node (ref "TP2") (pin "P$1") (pinfunction "TESTPOINT_P$1") (pintype "bidirectional"))
      (node (ref "U2") (pin "E4") (pinfunction "GPIO2/RXLED_E4") (pintype "bidirectional"))
    )
    (net (code "105") (name "Net-(TP3-TESTPOINT)") (class "Default")
      (node (ref "TP3") (pin "P$1") (pinfunction "TESTPOINT_P$1") (pintype "bidirectional"))
      (node (ref "U2") (pin "E2") (pinfunction "GPIO3/TXLED_E2") (pintype "bidirectional"))
    )
    (net (code "106") (name "Net-(TP4-TESTPOINT)") (class "Default")
      (node (ref "TP4") (pin "P$1") (pinfunction "TESTPOINT_P$1") (pintype "bidirectional"))
      (node (ref "U2") (pin "F1") (pinfunction "GPIO4/EXTPA_F1") (pintype "bidirectional"))
    )
    (net (code "107") (name "Net-(TP5-TESTPOINT)") (class "Default")
      (node (ref "TP5") (pin "P$1") (pinfunction "TESTPOINT_P$1") (pintype "bidirectional"))
      (node (ref "U2") (pin "D1") (pinfunction "GPIO5/EXTTXE/SPIPOL_D1") (pintype "bidirectional"))
    )
    (net (code "108") (name "Net-(U1-RFIOP)") (class "Default")
      (node (ref "CX5") (pin "1") (pinfunction "1_1") (pintype "passive"))
      (node (ref "L7") (pin "1") (pinfunction "1_1") (pintype "passive"))
      (node (ref "U1") (pin "M2") (pinfunction "RFIOP_M2") (pintype "bidirectional"))
    )
    (net (code "109") (name "Net-(U1-VDDBH_SW--BLE_BUCK_SW)") (class "Default")
      (node (ref "L6") (pin "1") (pinfunction "1_1") (pintype "bidirectional"))
      (node (ref "U1") (pin "H12") (pinfunction "VDDBH_SW--BLE_BUCK_SW_H12") (pintype "bidirectional"))
    )
    (net (code "110") (name "Net-(U1-XI)") (class "Default")
      (node (ref "C81") (pin "1") (pinfunction "1_1") (pintype "passive"))
      (node (ref "U1") (pin "A4") (pinfunction "XI_A4") (pintype "bidirectional"))
      (node (ref "X3") (pin "2") (pinfunction "2_2") (pintype "bidirectional"))
    )
    (net (code "111") (name "Net-(U1-XI32M)") (class "Default")
      (node (ref "CX4") (pin "1") (pinfunction "1_1") (pintype "passive"))
      (node (ref "U1") (pin "C12") (pinfunction "XI32M_C12") (pintype "bidirectional"))
      (node (ref "X1") (pin "3") (pinfunction "2_3") (pintype "bidirectional"))
    )
    (net (code "112") (name "Net-(U1-XO)") (class "Default")
      (node (ref "C80") (pin "1") (pinfunction "1_1") (pintype "passive"))
      (node (ref "U1") (pin "A5") (pinfunction "XO_A5") (pintype "bidirectional"))
      (node (ref "X3") (pin "1") (pinfunction "1_1") (pintype "bidirectional"))
    )
    (net (code "113") (name "Net-(U1-XO32M)") (class "Default")
      (node (ref "CX3") (pin "1") (pinfunction "1_1") (pintype "passive"))
      (node (ref "U1") (pin "D12") (pinfunction "XO32M_D12") (pintype "bidirectional"))
      (node (ref "X1") (pin "1") (pinfunction "1_1") (pintype "bidirectional"))
    )
    (net (code "114") (name "Net-(U2-RF2)") (class "Default")
      (node (ref "R1") (pin "1") (pinfunction "1_1") (pintype "passive"))
      (node (ref "U2") (pin "H5") (pinfunction "RF2_H5") (pintype "bidirectional"))
    )
    (net (code "115") (name "Net-(U2-VDD2A)") (class "Default")
      (node (ref "C12") (pin "P$1") (pinfunction "P$1_P$1") (pintype "bidirectional"))
      (node (ref "FB1") (pin "P$2") (pinfunction "P$2_P$2") (pintype "bidirectional"))
      (node (ref "U2") (pin "F15") (pinfunction "VDD2A_F15") (pintype "bidirectional"))
    )
    (net (code "116") (name "Net-(U2-VIO_D)") (class "Default")
      (node (ref "C23") (pin "1") (pinfunction "1_1") (pintype "bidirectional"))
      (node (ref "U2") (pin "A4") (pinfunction "VIO_D_A4") (pintype "bidirectional"))
    )
    (net (code "117") (name "Net-(U2-VTX_D)") (class "Default")
      (node (ref "C37") (pin "P$2") (pinfunction "P$2_P$2") (pintype "bidirectional"))
      (node (ref "U2") (pin "C14") (pinfunction "VTX_D_C14") (pintype "bidirectional"))
    )
    (net (code "118") (name "Net-(U2-XTI)") (class "Default")
      (node (ref "C3") (pin "P$1") (pinfunction "P$1_P$1") (pintype "bidirectional"))
      (node (ref "U2") (pin "H15") (pinfunction "XTI_H15") (pintype "bidirectional"))
      (node (ref "X4") (pin "1") (pinfunction "1_1") (pintype "bidirectional"))
    )
    (net (code "119") (name "Net-(U2-XTO)") (class "Default")
      (node (ref "C4") (pin "P$1") (pinfunction "P$1_P$1") (pintype "bidirectional"))
      (node (ref "U2") (pin "G14") (pinfunction "XTO_G14") (pintype "bidirectional"))
      (node (ref "X4") (pin "3") (pinfunction "2_3") (pintype "bidirectional"))
    )
    (net (code "120") (name "Net-(U3-ISET)") (class "Default")
      (node (ref "R15") (pin "2") (pinfunction "2_2") (pintype "passive"))
      (node (ref "U3") (pin "2") (pinfunction "ISET_2") (pintype "bidirectional"))
    )
    (net (code "121") (name "Net-(U3-PRETERM)") (class "Default")
      (node (ref "RX7") (pin "2") (pinfunction "2_2") (pintype "passive"))
      (node (ref "U3") (pin "4") (pinfunction "PRETERM_4") (pintype "bidirectional"))
    )
    (net (code "122") (name "Net-(U4-AC1)") (class "Default")
      (node (ref "C10") (pin "1") (pinfunction "1_1") (pintype "bidirectional"))
      (node (ref "C15") (pin "2") (pinfunction "2_2") (pintype "bidirectional"))
      (node (ref "C17") (pin "1") (pinfunction "1_1") (pintype "bidirectional"))
      (node (ref "C18") (pin "1") (pinfunction "1_1") (pintype "bidirectional"))
      (node (ref "C19") (pin "1") (pinfunction "1_1") (pintype "bidirectional"))
      (node (ref "C20") (pin "2") (pinfunction "2_2") (pintype "bidirectional"))
      (node (ref "C38") (pin "2") (pinfunction "2_2") (pintype "bidirectional"))
      (node (ref "C9") (pin "1") (pinfunction "1_1") (pintype "bidirectional"))
      (node (ref "U4") (pin "2") (pinfunction "AC1_2") (pintype "bidirectional"))
    )
    (net (code "123") (name "Net-(U4-BOOT1)") (class "Default")
      (node (ref "C15") (pin "1") (pinfunction "1_1") (pintype "bidirectional"))
      (node (ref "U4") (pin "3") (pinfunction "BOOT1_3") (pintype "bidirectional"))
    )
    (net (code "124") (name "Net-(U4-BOOT2)") (class "Default")
      (node (ref "C16") (pin "1") (pinfunction "1_1") (pintype "bidirectional"))
      (node (ref "U4") (pin "17") (pinfunction "BOOT2_17") (pintype "bidirectional"))
    )
    (net (code "125") (name "Net-(U4-CLAMP1)") (class "Default")
      (node (ref "C38") (pin "1") (pinfunction "1_1") (pintype "bidirectional"))
      (node (ref "U4") (pin "5") (pinfunction "CLAMP1_5") (pintype "bidirectional"))
    )
    (net (code "126") (name "Net-(U4-CLAMP2)") (class "Default")
      (node (ref "C39") (pin "1") (pinfunction "1_1") (pintype "bidirectional"))
      (node (ref "U4") (pin "16") (pinfunction "CLAMP2_16") (pintype "bidirectional"))
    )
    (net (code "127") (name "Net-(U4-COMM1)") (class "Default")
      (node (ref "C20") (pin "1") (pinfunction "1_1") (pintype "bidirectional"))
      (node (ref "U4") (pin "6") (pinfunction "COMM1_6") (pintype "bidirectional"))
    )
    (net (code "128") (name "Net-(U4-COMM2)") (class "Default")
      (node (ref "C21") (pin "1") (pinfunction "1_1") (pintype "bidirectional"))
      (node (ref "U4") (pin "15") (pinfunction "COMM2_15") (pintype "bidirectional"))
    )
    (net (code "129") (name "Net-(U4-FOD)") (class "Default")
      (node (ref "R23") (pin "2") (pinfunction "2_2") (pintype "passive"))
      (node (ref "R7") (pin "1") (pinfunction "1_1") (pintype "passive"))
      (node (ref "R9") (pin "2") (pinfunction "2_2") (pintype "passive"))
      (node (ref "U4") (pin "14") (pinfunction "FOD_14") (pintype "bidirectional"))
    )
    (net (code "130") (name "Net-(U4-ILIM)") (class "Default")
      (node (ref "R8") (pin "1") (pinfunction "1_1") (pintype "passive"))
      (node (ref "U4") (pin "12") (pinfunction "ILIM_12") (pintype "bidirectional"))
    )
    (net (code "131") (name "Net-(U4-RECT)") (class "Default")
      (node (ref "C28") (pin "1") (pinfunction "1_1") (pintype "bidirectional"))
      (node (ref "C56") (pin "1") (pinfunction "1_1") (pintype "bidirectional"))
      (node (ref "C57") (pin "1") (pinfunction "1_1") (pintype "bidirectional"))
      (node (ref "R18") (pin "1") (pinfunction "1_1") (pintype "passive"))
      (node (ref "U4") (pin "18") (pinfunction "RECT_18") (pintype "bidirectional"))
    )
    (net (code "132") (name "Net-(U6-CAP)") (class "Default")
      (node (ref "C36") (pin "1") (pinfunction "1_1") (pintype "bidirectional"))
      (node (ref "U6") (pin "9") (pinfunction "CAP_9") (pintype "bidirectional"))
    )
    (net (code "133") (name "Net-(U6-PS1)") (class "Default")
      (node (ref "RX9") (pin "2") (pinfunction "2_2") (pintype "passive"))
      (node (ref "RZ12") (pin "1") (pinfunction "1_1") (pintype "passive"))
      (node (ref "U6") (pin "5") (pinfunction "PS1_5") (pintype "input"))
    )
    (net (code "134") (name "Net-(U6-VDDIO)") (class "Default")
      (node (ref "C31") (pin "1") (pinfunction "1_1") (pintype "bidirectional"))
      (node (ref "U6") (pin "28") (pinfunction "VDDIO_28") (pintype "input"))
    )
    (net (code "135") (name "Net-(U7-VCTRL)") (class "Default")
      (node (ref "JP3") (pin "2") (pinfunction "2_2") (pintype "passive"))
      (node (ref "U7") (pin "8") (pinfunction "VCTRL_8") (pintype "bidirectional"))
    )
    (net (code "136") (name "Net-(U7-VDD)") (class "Default")
      (node (ref "C11") (pin "P$1") (pinfunction "P$1_P$1") (pintype "bidirectional"))
      (node (ref "C43") (pin "P$1") (pinfunction "P$1_P$1") (pintype "bidirectional"))
      (node (ref "RZ4") (pin "2") (pinfunction "2_2") (pintype "passive"))
      (node (ref "U7") (pin "1") (pinfunction "VDD_1") (pintype "bidirectional"))
    )
    (net (code "137") (name "Net-(VR2-EN)") (class "Default")
      (node (ref "RZ10") (pin "2") (pinfunction "2_2") (pintype "passive"))
      (node (ref "VR2") (pin "3") (pinfunction "EN_3") (pintype "input"))
    )
    (net (code "138") (name "Net-(XJ1-CC1)") (class "Default")
      (node (ref "XJ1") (pin "A5") (pinfunction "CC1_A5") (pintype "bidirectional"))
      (node (ref "XR16") (pin "1") (pinfunction "1_1") (pintype "passive"))
    )
    (net (code "139") (name "Net-(XJ1-CC2)") (class "Default")
      (node (ref "XJ1") (pin "B5") (pinfunction "CC2_B5") (pintype "bidirectional"))
      (node (ref "XR17") (pin "1") (pinfunction "1_1") (pintype "passive"))
    )
    (net (code "140") (name "RF1") (class "Default")
      (node (ref "S2") (pin "9") (pinfunction "J2_9") (pintype "bidirectional"))
      (node (ref "U7") (pin "6") (pinfunction "LNA_OUT_6") (pintype "bidirectional"))
    )
    (net (code "141") (name "RF2") (class "Default")
      (node (ref "A2") (pin "FEED") (pinfunction "ANTENNA_FEED") (pintype "bidirectional"))
      (node (ref "S2") (pin "3") (pinfunction "J3_3") (pintype "bidirectional"))
    )
    (net (code "142") (name "RF3") (class "Default")
      (node (ref "A3") (pin "FEED") (pinfunction "ANTENNA_FEED") (pintype "bidirectional"))
      (node (ref "S2") (pin "1") (pinfunction "J1_1") (pintype "bidirectional"))
      (node (ref "S4") (pin "IN") (pinfunction "IN_IN") (pintype "bidirectional"))
      (node (ref "S4") (pin "OUT") (pinfunction "A_OUT") (pintype "bidirectional"))
    )
    (net (code "143") (name "VBAT") (class "Default")
      (node (ref "C42") (pin "1") (pinfunction "1_1") (pintype "bidirectional"))
      (node (ref "J4") (pin "3") (pinfunction "3_3") (pintype "bidirectional"))
      (node (ref "J4") (pin "3SUPP") (pinfunction "3_3SUPP") (pintype "bidirectional"))
      (node (ref "JP9") (pin "1") (pinfunction "1_1") (pintype "passive"))
      (node (ref "S1") (pin "2") (pinfunction "2_2") (pintype "passive"))
      (node (ref "U3") (pin "10") (pinfunction "OUT_10") (pintype "bidirectional"))
    )
    (net (code "144") (name "VBAT_SWITCHED") (class "Default")
      (node (ref "C45") (pin "2") (pinfunction "2_2") (pintype "bidirectional"))
      (node (ref "C48") (pin "1") (pinfunction "1_1") (pintype "bidirectional"))
      (node (ref "R31") (pin "2") (pinfunction "2_2") (pintype "passive"))
      (node (ref "R33") (pin "1") (pinfunction "1_1") (pintype "passive"))
      (node (ref "R34") (pin "1") (pinfunction "1_1") (pintype "passive"))
      (node (ref "S1") (pin "3") (pinfunction "3_3") (pintype "passive"))
      (node (ref "VR1") (pin "1") (pinfunction "VIN2_1") (pintype "bidirectional"))
      (node (ref "VR1") (pin "7") (pinfunction "VIN1_7") (pintype "bidirectional"))
    )
    (net (code "145") (name "VDDAUDA_1P8-CLEAN") (class "Default")
      (node (ref "C72") (pin "P$1") (pinfunction "1_P$1") (pintype "bidirectional"))
      (node (ref "RZ11") (pin "2") (pinfunction "2_2") (pintype "passive"))
      (node (ref "U1") (pin "B11") (pinfunction "VDDAUDA_B11") (pintype "bidirectional"))
    )
    (net (code "146") (name "VQI") (class "Default")
      (node (ref "C29") (pin "1") (pinfunction "1_1") (pintype "bidirectional"))
      (node (ref "C41") (pin "1") (pinfunction "1_1") (pintype "bidirectional"))
      (node (ref "C53") (pin "1") (pinfunction "1_1") (pintype "bidirectional"))
      (node (ref "Q1") (pin "A2") (pinfunction "D1_A2") (pintype "bidirectional"))
      (node (ref "Q1") (pin "A3") (pinfunction "D1_A3") (pintype "bidirectional"))
      (node (ref "Q1") (pin "B3") (pinfunction "D1_B3") (pintype "bidirectional"))
      (node (ref "U3") (pin "1") (pinfunction "IN_1") (pintype "bidirectional"))
      (node (ref "U4") (pin "4") (pinfunction "OUT_4") (pintype "bidirectional"))
    )
    (net (code "147") (name "VR1_1P8_EN") (class "Default")
      (node (ref "R34") (pin "2") (pinfunction "2_2") (pintype "passive"))
      (node (ref "VR1") (pin "6") (pinfunction "EN1_6") (pintype "bidirectional"))
    )
    (net (code "148") (name "VR1_2P5_EN") (class "Default")
      (node (ref "R33") (pin "2") (pinfunction "2_2") (pintype "passive"))
      (node (ref "VR1") (pin "12") (pinfunction "EN2_12") (pintype "bidirectional"))
    )
    (net (code "149") (name "VUSB") (class "Default")
      (node (ref "C40") (pin "2") (pinfunction "2_2") (pintype "bidirectional"))
      (node (ref "Q1") (pin "B2") (pinfunction "D2_B2") (pintype "bidirectional"))
      (node (ref "Q1") (pin "C2") (pinfunction "D2_C2") (pintype "bidirectional"))
      (node (ref "Q1") (pin "C3") (pinfunction "D2_C3") (pintype "bidirectional"))
      (node (ref "U4") (pin "9") (pinfunction "AD_9") (pintype "bidirectional"))
      (node (ref "XJ1") (pin "A4/B9") (pinfunction "VBUS_A4/B9") (pintype "power_in"))
      (node (ref "XJ1") (pin "B4/A9") (pinfunction "VBUS_B4/A9") (pintype "power_in"))
    )
    (net (code "150") (name "unconnected-(Q1-S-PadB1)") (class "Default")
      (node (ref "Q1") (pin "B1") (pinfunction "S_B1") (pintype "bidirectional"))
    )
    (net (code "151") (name "unconnected-(S1-Pad1)") (class "Default")
      (node (ref "S1") (pin "1") (pinfunction "1_1") (pintype "passive"))
    )
    (net (code "152") (name "unconnected-(U1-GPIO0-PadH3)") (class "Default")
      (node (ref "U1") (pin "H3") (pinfunction "GPIO0_H3") (pintype "bidirectional"))
    )
    (net (code "153") (name "unconnected-(U1-GPIO1-PadJ4)") (class "Default")
      (node (ref "U1") (pin "J4") (pinfunction "GPIO1_J4") (pintype "bidirectional"))
    )
    (net (code "154") (name "unconnected-(U1-GPIO2-PadK4)") (class "Default")
      (node (ref "U1") (pin "K4") (pinfunction "GPIO2_K4") (pintype "bidirectional"))
    )
    (net (code "155") (name "unconnected-(U1-GPIO4-PadM4)") (class "Default")
      (node (ref "U1") (pin "M4") (pinfunction "GPIO4_M4") (pintype "bidirectional"))
    )
    (net (code "156") (name "unconnected-(U1-GPIO5-PadH4)") (class "Default")
      (node (ref "U1") (pin "H4") (pinfunction "GPIO5_H4") (pintype "bidirectional"))
    )
    (net (code "157") (name "unconnected-(U1-GPIO7-PadJ6)") (class "Default")
      (node (ref "U1") (pin "J6") (pinfunction "GPIO7_J6") (pintype "bidirectional"))
    )
    (net (code "158") (name "unconnected-(U1-GPIO11-PadE4)") (class "Default")
      (node (ref "U1") (pin "E4") (pinfunction "GPIO11_E4") (pintype "bidirectional"))
    )
    (net (code "159") (name "unconnected-(U1-GPIO12-PadB4)") (class "Default")
      (node (ref "U1") (pin "B4") (pinfunction "GPIO12_B4") (pintype "bidirectional"))
    )
    (net (code "160") (name "unconnected-(U1-GPIO15-PadE5)") (class "Default")
      (node (ref "U1") (pin "E5") (pinfunction "GPIO15_E5") (pintype "bidirectional"))
    )
    (net (code "161") (name "unconnected-(U1-GPIO16-PadD7)") (class "Default")
      (node (ref "U1") (pin "D7") (pinfunction "GPIO16_D7") (pintype "bidirectional"))
    )
    (net (code "162") (name "unconnected-(U1-GPIO19-PadC3)") (class "Default")
      (node (ref "U1") (pin "C3") (pinfunction "GPIO19_C3") (pintype "bidirectional"))
    )
    (net (code "163") (name "unconnected-(U1-GPIO22-PadF3)") (class "Default")
      (node (ref "U1") (pin "F3") (pinfunction "GPIO22_F3") (pintype "bidirectional"))
    )
    (net (code "164") (name "unconnected-(U1-GPIO23-PadF2)") (class "Default")
      (node (ref "U1") (pin "F2") (pinfunction "GPIO23_F2") (pintype "bidirectional"))
    )
    (net (code "165") (name "unconnected-(U1-GPIO28-PadE3)") (class "Default")
      (node (ref "U1") (pin "E3") (pinfunction "GPIO28_E3") (pintype "bidirectional"))
    )
    (net (code "166") (name "unconnected-(U1-GPIO29-PadF4)") (class "Default")
      (node (ref "U1") (pin "F4") (pinfunction "GPIO29_F4") (pintype "bidirectional"))
    )
    (net (code "167") (name "unconnected-(U1-GPIO37-PadF11)") (class "Default")
      (node (ref "U1") (pin "F11") (pinfunction "GPIO37_F11") (pintype "bidirectional"))
    )
    (net (code "168") (name "unconnected-(U1-GPIO52-PadC10)") (class "Default")
      (node (ref "U1") (pin "C10") (pinfunction "GPIO52_C10") (pintype "bidirectional"))
    )
    (net (code "169") (name "unconnected-(U1-GPIO54-PadD10)") (class "Default")
      (node (ref "U1") (pin "D10") (pinfunction "GPIO54_D10") (pintype "bidirectional"))
    )
    (net (code "170") (name "unconnected-(U1-GPIO56-PadE10)") (class "Default")
      (node (ref "U1") (pin "E10") (pinfunction "GPIO56_E10") (pintype "bidirectional"))
    )
    (net (code "171") (name "unconnected-(U1-GPIO57-PadE9)") (class "Default")
      (node (ref "U1") (pin "E9") (pinfunction "GPIO57_E9") (pintype "bidirectional"))
    )
    (net (code "172") (name "unconnected-(U1-GPIO59-PadJ8)") (class "Default")
      (node (ref "U1") (pin "J8") (pinfunction "GPIO59_J8") (pintype "bidirectional"))
    )
    (net (code "173") (name "unconnected-(U1-GPIO61-PadK6)") (class "Default")
      (node (ref "U1") (pin "K6") (pinfunction "GPIO61_K6") (pintype "bidirectional"))
    )
    (net (code "174") (name "unconnected-(U1-GPIO62-PadL6)") (class "Default")
      (node (ref "U1") (pin "L6") (pinfunction "GPIO62_L6") (pintype "bidirectional"))
    )
    (net (code "175") (name "unconnected-(U1-GPIO64-PadB6)") (class "Default")
      (node (ref "U1") (pin "B6") (pinfunction "GPIO64_B6") (pintype "bidirectional"))
    )
    (net (code "176") (name "unconnected-(U1-GPIO67-PadC6)") (class "Default")
      (node (ref "U1") (pin "C6") (pinfunction "GPIO67_C6") (pintype "bidirectional"))
    )
    (net (code "177") (name "unconnected-(U1-GPIO68-PadB7)") (class "Default")
      (node (ref "U1") (pin "B7") (pinfunction "GPIO68_B7") (pintype "bidirectional"))
    )
    (net (code "178") (name "unconnected-(U1-GPIO70-PadC5)") (class "Default")
      (node (ref "U1") (pin "C5") (pinfunction "GPIO70_C5") (pintype "bidirectional"))
    )
    (net (code "179") (name "unconnected-(U1-GPIO71-PadC7)") (class "Default")
      (node (ref "U1") (pin "C7") (pinfunction "GPIO71_C7") (pintype "bidirectional"))
    )
    (net (code "180") (name "unconnected-(U1-GPIO73-PadD8)") (class "Default")
      (node (ref "U1") (pin "D8") (pinfunction "GPIO73_D8") (pintype "bidirectional"))
    )
    (net (code "181") (name "unconnected-(U1-GPIO74-PadG11)") (class "Default")
      (node (ref "U1") (pin "G11") (pinfunction "GPIO74_G11") (pintype "bidirectional"))
    )
    (net (code "182") (name "unconnected-(U1-GPIO75-PadH11)") (class "Default")
      (node (ref "U1") (pin "H11") (pinfunction "GPIO75_H11") (pintype "bidirectional"))
    )
    (net (code "183") (name "unconnected-(U1-GPIO76-PadJ11)") (class "Default")
      (node (ref "U1") (pin "J11") (pinfunction "GPIO76_J11") (pintype "bidirectional"))
    )
    (net (code "184") (name "unconnected-(U1-GPIO77-PadK11)") (class "Default")
      (node (ref "U1") (pin "K11") (pinfunction "GPIO77_K11") (pintype "bidirectional"))
    )
    (net (code "185") (name "unconnected-(U1-GPIO78-PadL11)") (class "Default")
      (node (ref "U1") (pin "L11") (pinfunction "GPIO78_L11") (pintype "bidirectional"))
    )
    (net (code "186") (name "unconnected-(U1-GPIO84-PadJ9)") (class "Default")
      (node (ref "U1") (pin "J9") (pinfunction "GPIO84_J9") (pintype "bidirectional"))
    )
    (net (code "187") (name "unconnected-(U1-GPIO85-PadH9)") (class "Default")
      (node (ref "U1") (pin "H9") (pinfunction "GPIO85_H9") (pintype "bidirectional"))
    )
    (net (code "188") (name "unconnected-(U1-GPIO86-PadG10)") (class "Default")
      (node (ref "U1") (pin "G10") (pinfunction "GPIO86_G10") (pintype "bidirectional"))
    )
    (net (code "189") (name "unconnected-(U1-GPIO87-PadG9)") (class "Default")
      (node (ref "U1") (pin "G9") (pinfunction "GPIO87_G9") (pintype "bidirectional"))
    )
    (net (code "190") (name "unconnected-(U1-GPIO89-PadF10)") (class "Default")
      (node (ref "U1") (pin "F10") (pinfunction "GPIO89_F10") (pintype "bidirectional"))
    )
    (net (code "191") (name "unconnected-(U1-GPIO90-PadJ2)") (class "Default")
      (node (ref "U1") (pin "J2") (pinfunction "GPIO90_J2") (pintype "bidirectional"))
    )
    (net (code "192") (name "unconnected-(U1-GPIO91-PadK2)") (class "Default")
      (node (ref "U1") (pin "K2") (pinfunction "GPIO91_K2") (pintype "bidirectional"))
    )
    (net (code "193") (name "unconnected-(U1-LPADC_D0NSE0-PadA10)") (class "Default")
      (node (ref "U1") (pin "A10") (pinfunction "LPADC_D0NSE0_A10") (pintype "input"))
    )
    (net (code "194") (name "unconnected-(U1-LPADC_D0PSE1-PadA11)") (class "Default")
      (node (ref "U1") (pin "A11") (pinfunction "LPADC_D0PSE1_A11") (pintype "input"))
    )
    (net (code "195") (name "unconnected-(U1-LPADC_D1NSE2-PadC11)") (class "Default")
      (node (ref "U1") (pin "C11") (pinfunction "LPADC_D1NSE2_C11") (pintype "input"))
    )
    (net (code "196") (name "unconnected-(U1-LPADC_D1PSE3-PadD11)") (class "Default")
      (node (ref "U1") (pin "D11") (pinfunction "LPADC_D1PSE3_D11") (pintype "input"))
    )
    (net (code "197") (name "unconnected-(U1-MIPI_CLKN-PadJ12)") (class "Default")
      (node (ref "U1") (pin "J12") (pinfunction "MIPI_CLKN_J12") (pintype "bidirectional"))
    )
    (net (code "198") (name "unconnected-(U1-MIPI_CLKP-PadK12)") (class "Default")
      (node (ref "U1") (pin "K12") (pinfunction "MIPI_CLKP_K12") (pintype "bidirectional"))
    )
    (net (code "199") (name "unconnected-(U1-MIPI_DON-PadL12)") (class "Default")
      (node (ref "U1") (pin "L12") (pinfunction "MIPI_DON_L12") (pintype "bidirectional"))
    )
    (net (code "200") (name "unconnected-(U1-MIPI_DOP-PadM12)") (class "Default")
      (node (ref "U1") (pin "M12") (pinfunction "MIPI_DOP_M12") (pintype "bidirectional"))
    )
    (net (code "201") (name "unconnected-(U1-TXEN-PadK1)") (class "Default")
      (node (ref "U1") (pin "K1") (pinfunction "TXEN_K1") (pintype "output"))
    )
    (net (code "202") (name "unconnected-(VR1-NC1-Pad5)") (class "Default")
      (node (ref "VR1") (pin "5") (pinfunction "NC1_5") (pintype "bidirectional"))
    )
    (net (code "203") (name "unconnected-(VR1-NC2-Pad11)") (class "Default")
      (node (ref "VR1") (pin "11") (pinfunction "NC2_11") (pintype "bidirectional"))
    )
    (net (code "204") (name "unconnected-(XJ1-SBU1-PadA8)") (class "Default")
      (node (ref "XJ1") (pin "A8") (pinfunction "SBU1_A8") (pintype "bidirectional"))
    )
    (net (code "205") (name "unconnected-(XJ1-SBU2-PadB8)") (class "Default")
      (node (ref "XJ1") (pin "B8") (pinfunction "SBU2_B8") (pintype "bidirectional"))
    )
    (net (code "206") (name "~{AD_EN}") (class "Default")
      (node (ref "Q1") (pin "A1") (pinfunction "G1_A1") (pintype "input"))
      (node (ref "Q1") (pin "C1") (pinfunction "G2_C1") (pintype "input"))
      (node (ref "U4") (pin "8") (pinfunction "~{AD-EN}_8") (pintype "bidirectional"))
    )
  )
)
